# MINI_MAST.net
KiCad netlist of a schematic drawn in EAGLE
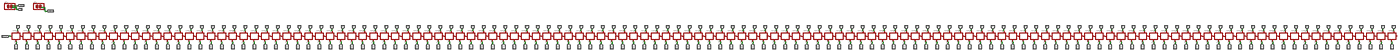
[diagram p0: schematic, sheet 1, overview]
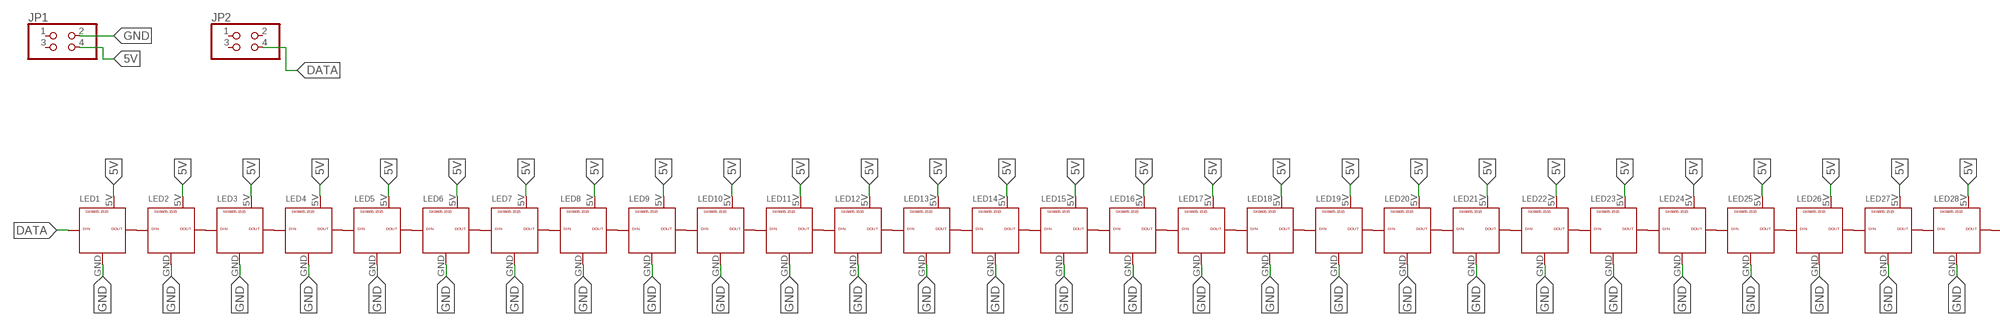
[diagram p1: schematic, sheet 1, part 1 of 6]
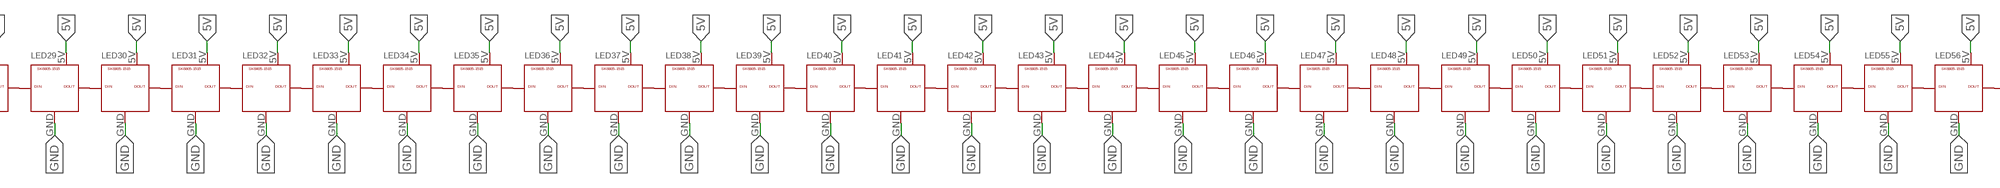
[diagram p2: schematic, sheet 1, part 2 of 6]
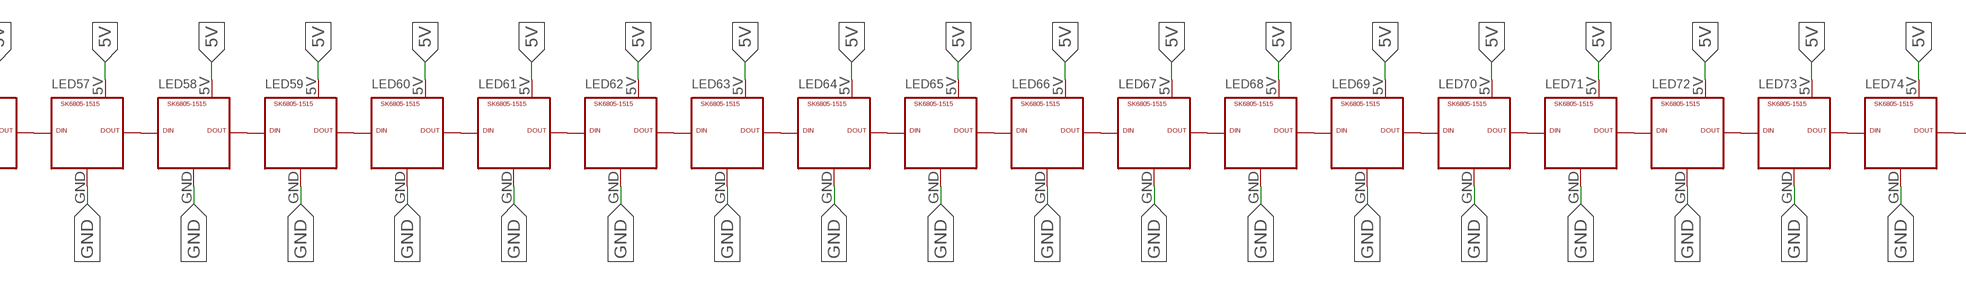
[diagram p3: schematic, sheet 1, part 3 of 6]
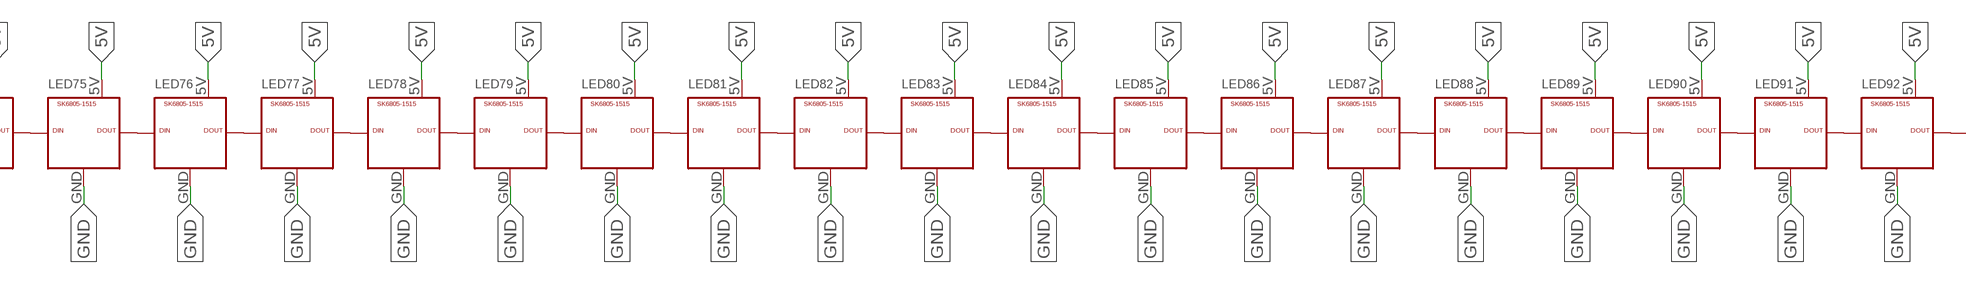
[diagram p4: schematic, sheet 1, part 4 of 6]
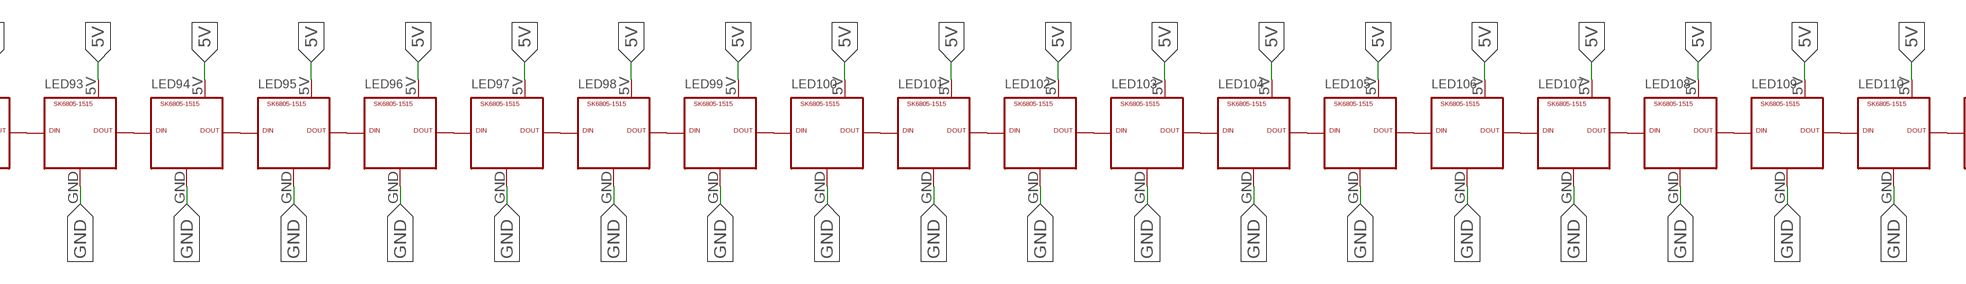
[diagram p5: schematic, sheet 1, part 5 of 6]
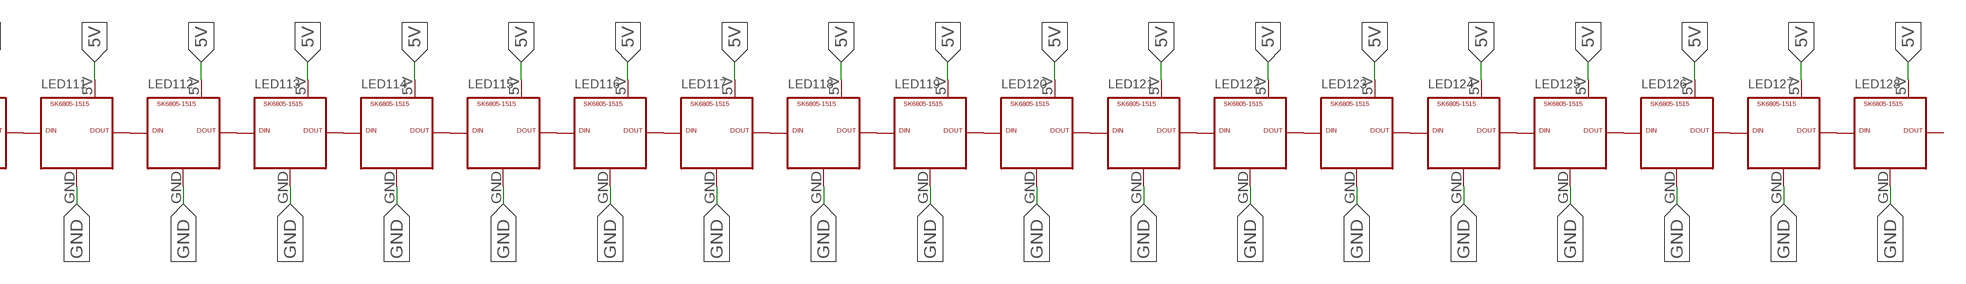
[diagram p6: schematic, sheet 1, part 6 of 6]

(export (version "E")
  (design (tool "Eeschema 10.0.6"))
  (components
    (comp (ref "JP1")
      (value "PINHD-2X2/90")
      (footprint "eagle-import:2X02_90")
      (libsource (lib "eagle-import") (part "PINHD-2X2/90"))
    )
    (comp (ref "JP2")
      (value "PINHD-2X2/90")
      (footprint "eagle-import:2X02_90")
      (libsource (lib "eagle-import") (part "PINHD-2X2/90"))
    )
    (comp (ref "LED1")
      (value "SK6805-1515")
      (footprint "eagle-import:1515")
      (libsource (lib "eagle-import") (part "SK6805-1515"))
    )
    (comp (ref "LED2")
      (value "SK6805-1515")
      (footprint "eagle-import:1515")
      (libsource (lib "eagle-import") (part "SK6805-1515"))
    )
    (comp (ref "LED3")
      (value "SK6805-1515")
      (footprint "eagle-import:1515")
      (libsource (lib "eagle-import") (part "SK6805-1515"))
    )
    (comp (ref "LED4")
      (value "SK6805-1515")
      (footprint "eagle-import:1515")
      (libsource (lib "eagle-import") (part "SK6805-1515"))
    )
    (comp (ref "LED5")
      (value "SK6805-1515")
      (footprint "eagle-import:1515")
      (libsource (lib "eagle-import") (part "SK6805-1515"))
    )
    (comp (ref "LED6")
      (value "SK6805-1515")
      (footprint "eagle-import:1515")
      (libsource (lib "eagle-import") (part "SK6805-1515"))
    )
    (comp (ref "LED7")
      (value "SK6805-1515")
      (footprint "eagle-import:1515")
      (libsource (lib "eagle-import") (part "SK6805-1515"))
    )
    (comp (ref "LED8")
      (value "SK6805-1515")
      (footprint "eagle-import:1515")
      (libsource (lib "eagle-import") (part "SK6805-1515"))
    )
    (comp (ref "LED9")
      (value "SK6805-1515")
      (footprint "eagle-import:1515")
      (libsource (lib "eagle-import") (part "SK6805-1515"))
    )
    (comp (ref "LED10")
      (value "SK6805-1515")
      (footprint "eagle-import:1515")
      (libsource (lib "eagle-import") (part "SK6805-1515"))
    )
    (comp (ref "LED11")
      (value "SK6805-1515")
      (footprint "eagle-import:1515")
      (libsource (lib "eagle-import") (part "SK6805-1515"))
    )
    (comp (ref "LED12")
      (value "SK6805-1515")
      (footprint "eagle-import:1515")
      (libsource (lib "eagle-import") (part "SK6805-1515"))
    )
    (comp (ref "LED13")
      (value "SK6805-1515")
      (footprint "eagle-import:1515")
      (libsource (lib "eagle-import") (part "SK6805-1515"))
    )
    (comp (ref "LED14")
      (value "SK6805-1515")
      (footprint "eagle-import:1515")
      (libsource (lib "eagle-import") (part "SK6805-1515"))
    )
    (comp (ref "LED15")
      (value "SK6805-1515")
      (footprint "eagle-import:1515")
      (libsource (lib "eagle-import") (part "SK6805-1515"))
    )
    (comp (ref "LED16")
      (value "SK6805-1515")
      (footprint "eagle-import:1515")
      (libsource (lib "eagle-import") (part "SK6805-1515"))
    )
    (comp (ref "LED17")
      (value "SK6805-1515")
      (footprint "eagle-import:1515")
      (libsource (lib "eagle-import") (part "SK6805-1515"))
    )
    (comp (ref "LED18")
      (value "SK6805-1515")
      (footprint "eagle-import:1515")
      (libsource (lib "eagle-import") (part "SK6805-1515"))
    )
    (comp (ref "LED19")
      (value "SK6805-1515")
      (footprint "eagle-import:1515")
      (libsource (lib "eagle-import") (part "SK6805-1515"))
    )
    (comp (ref "LED20")
      (value "SK6805-1515")
      (footprint "eagle-import:1515")
      (libsource (lib "eagle-import") (part "SK6805-1515"))
    )
    (comp (ref "LED21")
      (value "SK6805-1515")
      (footprint "eagle-import:1515")
      (libsource (lib "eagle-import") (part "SK6805-1515"))
    )
    (comp (ref "LED22")
      (value "SK6805-1515")
      (footprint "eagle-import:1515")
      (libsource (lib "eagle-import") (part "SK6805-1515"))
    )
    (comp (ref "LED23")
      (value "SK6805-1515")
      (footprint "eagle-import:1515")
      (libsource (lib "eagle-import") (part "SK6805-1515"))
    )
    (comp (ref "LED24")
      (value "SK6805-1515")
      (footprint "eagle-import:1515")
      (libsource (lib "eagle-import") (part "SK6805-1515"))
    )
    (comp (ref "LED25")
      (value "SK6805-1515")
      (footprint "eagle-import:1515")
      (libsource (lib "eagle-import") (part "SK6805-1515"))
    )
    (comp (ref "LED26")
      (value "SK6805-1515")
      (footprint "eagle-import:1515")
      (libsource (lib "eagle-import") (part "SK6805-1515"))
    )
    (comp (ref "LED27")
      (value "SK6805-1515")
      (footprint "eagle-import:1515")
      (libsource (lib "eagle-import") (part "SK6805-1515"))
    )
    (comp (ref "LED28")
      (value "SK6805-1515")
      (footprint "eagle-import:1515")
      (libsource (lib "eagle-import") (part "SK6805-1515"))
    )
    (comp (ref "LED29")
      (value "SK6805-1515")
      (footprint "eagle-import:1515")
      (libsource (lib "eagle-import") (part "SK6805-1515"))
    )
    (comp (ref "LED30")
      (value "SK6805-1515")
      (footprint "eagle-import:1515")
      (libsource (lib "eagle-import") (part "SK6805-1515"))
    )
    (comp (ref "LED31")
      (value "SK6805-1515")
      (footprint "eagle-import:1515")
      (libsource (lib "eagle-import") (part "SK6805-1515"))
    )
    (comp (ref "LED32")
      (value "SK6805-1515")
      (footprint "eagle-import:1515")
      (libsource (lib "eagle-import") (part "SK6805-1515"))
    )
    (comp (ref "LED33")
      (value "SK6805-1515")
      (footprint "eagle-import:1515")
      (libsource (lib "eagle-import") (part "SK6805-1515"))
    )
    (comp (ref "LED34")
      (value "SK6805-1515")
      (footprint "eagle-import:1515")
      (libsource (lib "eagle-import") (part "SK6805-1515"))
    )
    (comp (ref "LED35")
      (value "SK6805-1515")
      (footprint "eagle-import:1515")
      (libsource (lib "eagle-import") (part "SK6805-1515"))
    )
    (comp (ref "LED36")
      (value "SK6805-1515")
      (footprint "eagle-import:1515")
      (libsource (lib "eagle-import") (part "SK6805-1515"))
    )
    (comp (ref "LED37")
      (value "SK6805-1515")
      (footprint "eagle-import:1515")
      (libsource (lib "eagle-import") (part "SK6805-1515"))
    )
    (comp (ref "LED38")
      (value "SK6805-1515")
      (footprint "eagle-import:1515")
      (libsource (lib "eagle-import") (part "SK6805-1515"))
    )
    (comp (ref "LED39")
      (value "SK6805-1515")
      (footprint "eagle-import:1515")
      (libsource (lib "eagle-import") (part "SK6805-1515"))
    )
    (comp (ref "LED40")
      (value "SK6805-1515")
      (footprint "eagle-import:1515")
      (libsource (lib "eagle-import") (part "SK6805-1515"))
    )
    (comp (ref "LED41")
      (value "SK6805-1515")
      (footprint "eagle-import:1515")
      (libsource (lib "eagle-import") (part "SK6805-1515"))
    )
    (comp (ref "LED42")
      (value "SK6805-1515")
      (footprint "eagle-import:1515")
      (libsource (lib "eagle-import") (part "SK6805-1515"))
    )
    (comp (ref "LED43")
      (value "SK6805-1515")
      (footprint "eagle-import:1515")
      (libsource (lib "eagle-import") (part "SK6805-1515"))
    )
    (comp (ref "LED44")
      (value "SK6805-1515")
      (footprint "eagle-import:1515")
      (libsource (lib "eagle-import") (part "SK6805-1515"))
    )
    (comp (ref "LED45")
      (value "SK6805-1515")
      (footprint "eagle-import:1515")
      (libsource (lib "eagle-import") (part "SK6805-1515"))
    )
    (comp (ref "LED46")
      (value "SK6805-1515")
      (footprint "eagle-import:1515")
      (libsource (lib "eagle-import") (part "SK6805-1515"))
    )
    (comp (ref "LED47")
      (value "SK6805-1515")
      (footprint "eagle-import:1515")
      (libsource (lib "eagle-import") (part "SK6805-1515"))
    )
    (comp (ref "LED48")
      (value "SK6805-1515")
      (footprint "eagle-import:1515")
      (libsource (lib "eagle-import") (part "SK6805-1515"))
    )
    (comp (ref "LED49")
      (value "SK6805-1515")
      (footprint "eagle-import:1515")
      (libsource (lib "eagle-import") (part "SK6805-1515"))
    )
    (comp (ref "LED50")
      (value "SK6805-1515")
      (footprint "eagle-import:1515")
      (libsource (lib "eagle-import") (part "SK6805-1515"))
    )
    (comp (ref "LED51")
      (value "SK6805-1515")
      (footprint "eagle-import:1515")
      (libsource (lib "eagle-import") (part "SK6805-1515"))
    )
    (comp (ref "LED52")
      (value "SK6805-1515")
      (footprint "eagle-import:1515")
      (libsource (lib "eagle-import") (part "SK6805-1515"))
    )
    (comp (ref "LED53")
      (value "SK6805-1515")
      (footprint "eagle-import:1515")
      (libsource (lib "eagle-import") (part "SK6805-1515"))
    )
    (comp (ref "LED54")
      (value "SK6805-1515")
      (footprint "eagle-import:1515")
      (libsource (lib "eagle-import") (part "SK6805-1515"))
    )
    (comp (ref "LED55")
      (value "SK6805-1515")
      (footprint "eagle-import:1515")
      (libsource (lib "eagle-import") (part "SK6805-1515"))
    )
    (comp (ref "LED56")
      (value "SK6805-1515")
      (footprint "eagle-import:1515")
      (libsource (lib "eagle-import") (part "SK6805-1515"))
    )
    (comp (ref "LED57")
      (value "SK6805-1515")
      (footprint "eagle-import:1515")
      (libsource (lib "eagle-import") (part "SK6805-1515"))
    )
    (comp (ref "LED58")
      (value "SK6805-1515")
      (footprint "eagle-import:1515")
      (libsource (lib "eagle-import") (part "SK6805-1515"))
    )
    (comp (ref "LED59")
      (value "SK6805-1515")
      (footprint "eagle-import:1515")
      (libsource (lib "eagle-import") (part "SK6805-1515"))
    )
    (comp (ref "LED60")
      (value "SK6805-1515")
      (footprint "eagle-import:1515")
      (libsource (lib "eagle-import") (part "SK6805-1515"))
    )
    (comp (ref "LED61")
      (value "SK6805-1515")
      (footprint "eagle-import:1515")
      (libsource (lib "eagle-import") (part "SK6805-1515"))
    )
    (comp (ref "LED62")
      (value "SK6805-1515")
      (footprint "eagle-import:1515")
      (libsource (lib "eagle-import") (part "SK6805-1515"))
    )
    (comp (ref "LED63")
      (value "SK6805-1515")
      (footprint "eagle-import:1515")
      (libsource (lib "eagle-import") (part "SK6805-1515"))
    )
    (comp (ref "LED64")
      (value "SK6805-1515")
      (footprint "eagle-import:1515")
      (libsource (lib "eagle-import") (part "SK6805-1515"))
    )
    (comp (ref "LED65")
      (value "SK6805-1515")
      (footprint "eagle-import:1515")
      (libsource (lib "eagle-import") (part "SK6805-1515"))
    )
    (comp (ref "LED66")
      (value "SK6805-1515")
      (footprint "eagle-import:1515")
      (libsource (lib "eagle-import") (part "SK6805-1515"))
    )
    (comp (ref "LED67")
      (value "SK6805-1515")
      (footprint "eagle-import:1515")
      (libsource (lib "eagle-import") (part "SK6805-1515"))
    )
    (comp (ref "LED68")
      (value "SK6805-1515")
      (footprint "eagle-import:1515")
      (libsource (lib "eagle-import") (part "SK6805-1515"))
    )
    (comp (ref "LED69")
      (value "SK6805-1515")
      (footprint "eagle-import:1515")
      (libsource (lib "eagle-import") (part "SK6805-1515"))
    )
    (comp (ref "LED70")
      (value "SK6805-1515")
      (footprint "eagle-import:1515")
      (libsource (lib "eagle-import") (part "SK6805-1515"))
    )
    (comp (ref "LED71")
      (value "SK6805-1515")
      (footprint "eagle-import:1515")
      (libsource (lib "eagle-import") (part "SK6805-1515"))
    )
    (comp (ref "LED72")
      (value "SK6805-1515")
      (footprint "eagle-import:1515")
      (libsource (lib "eagle-import") (part "SK6805-1515"))
    )
    (comp (ref "LED73")
      (value "SK6805-1515")
      (footprint "eagle-import:1515")
      (libsource (lib "eagle-import") (part "SK6805-1515"))
    )
    (comp (ref "LED74")
      (value "SK6805-1515")
      (footprint "eagle-import:1515")
      (libsource (lib "eagle-import") (part "SK6805-1515"))
    )
    (comp (ref "LED75")
      (value "SK6805-1515")
      (footprint "eagle-import:1515")
      (libsource (lib "eagle-import") (part "SK6805-1515"))
    )
    (comp (ref "LED76")
      (value "SK6805-1515")
      (footprint "eagle-import:1515")
      (libsource (lib "eagle-import") (part "SK6805-1515"))
    )
    (comp (ref "LED77")
      (value "SK6805-1515")
      (footprint "eagle-import:1515")
      (libsource (lib "eagle-import") (part "SK6805-1515"))
    )
    (comp (ref "LED78")
      (value "SK6805-1515")
      (footprint "eagle-import:1515")
      (libsource (lib "eagle-import") (part "SK6805-1515"))
    )
    (comp (ref "LED79")
      (value "SK6805-1515")
      (footprint "eagle-import:1515")
      (libsource (lib "eagle-import") (part "SK6805-1515"))
    )
    (comp (ref "LED80")
      (value "SK6805-1515")
      (footprint "eagle-import:1515")
      (libsource (lib "eagle-import") (part "SK6805-1515"))
    )
    (comp (ref "LED81")
      (value "SK6805-1515")
      (footprint "eagle-import:1515")
      (libsource (lib "eagle-import") (part "SK6805-1515"))
    )
    (comp (ref "LED82")
      (value "SK6805-1515")
      (footprint "eagle-import:1515")
      (libsource (lib "eagle-import") (part "SK6805-1515"))
    )
    (comp (ref "LED83")
      (value "SK6805-1515")
      (footprint "eagle-import:1515")
      (libsource (lib "eagle-import") (part "SK6805-1515"))
    )
    (comp (ref "LED84")
      (value "SK6805-1515")
      (footprint "eagle-import:1515")
      (libsource (lib "eagle-import") (part "SK6805-1515"))
    )
    (comp (ref "LED85")
      (value "SK6805-1515")
      (footprint "eagle-import:1515")
      (libsource (lib "eagle-import") (part "SK6805-1515"))
    )
    (comp (ref "LED86")
      (value "SK6805-1515")
      (footprint "eagle-import:1515")
      (libsource (lib "eagle-import") (part "SK6805-1515"))
    )
    (comp (ref "LED87")
      (value "SK6805-1515")
      (footprint "eagle-import:1515")
      (libsource (lib "eagle-import") (part "SK6805-1515"))
    )
    (comp (ref "LED88")
      (value "SK6805-1515")
      (footprint "eagle-import:1515")
      (libsource (lib "eagle-import") (part "SK6805-1515"))
    )
    (comp (ref "LED89")
      (value "SK6805-1515")
      (footprint "eagle-import:1515")
      (libsource (lib "eagle-import") (part "SK6805-1515"))
    )
    (comp (ref "LED90")
      (value "SK6805-1515")
      (footprint "eagle-import:1515")
      (libsource (lib "eagle-import") (part "SK6805-1515"))
    )
    (comp (ref "LED91")
      (value "SK6805-1515")
      (footprint "eagle-import:1515")
      (libsource (lib "eagle-import") (part "SK6805-1515"))
    )
    (comp (ref "LED92")
      (value "SK6805-1515")
      (footprint "eagle-import:1515")
      (libsource (lib "eagle-import") (part "SK6805-1515"))
    )
    (comp (ref "LED93")
      (value "SK6805-1515")
      (footprint "eagle-import:1515")
      (libsource (lib "eagle-import") (part "SK6805-1515"))
    )
    (comp (ref "LED94")
      (value "SK6805-1515")
      (footprint "eagle-import:1515")
      (libsource (lib "eagle-import") (part "SK6805-1515"))
    )
    (comp (ref "LED95")
      (value "SK6805-1515")
      (footprint "eagle-import:1515")
      (libsource (lib "eagle-import") (part "SK6805-1515"))
    )
    (comp (ref "LED96")
      (value "SK6805-1515")
      (footprint "eagle-import:1515")
      (libsource (lib "eagle-import") (part "SK6805-1515"))
    )
    (comp (ref "LED97")
      (value "SK6805-1515")
      (footprint "eagle-import:1515")
      (libsource (lib "eagle-import") (part "SK6805-1515"))
    )
    (comp (ref "LED98")
      (value "SK6805-1515")
      (footprint "eagle-import:1515")
      (libsource (lib "eagle-import") (part "SK6805-1515"))
    )
    (comp (ref "LED99")
      (value "SK6805-1515")
      (footprint "eagle-import:1515")
      (libsource (lib "eagle-import") (part "SK6805-1515"))
    )
    (comp (ref "LED100")
      (value "SK6805-1515")
      (footprint "eagle-import:1515")
      (libsource (lib "eagle-import") (part "SK6805-1515"))
    )
    (comp (ref "LED101")
      (value "SK6805-1515")
      (footprint "eagle-import:1515")
      (libsource (lib "eagle-import") (part "SK6805-1515"))
    )
    (comp (ref "LED102")
      (value "SK6805-1515")
      (footprint "eagle-import:1515")
      (libsource (lib "eagle-import") (part "SK6805-1515"))
    )
    (comp (ref "LED103")
      (value "SK6805-1515")
      (footprint "eagle-import:1515")
      (libsource (lib "eagle-import") (part "SK6805-1515"))
    )
    (comp (ref "LED104")
      (value "SK6805-1515")
      (footprint "eagle-import:1515")
      (libsource (lib "eagle-import") (part "SK6805-1515"))
    )
    (comp (ref "LED105")
      (value "SK6805-1515")
      (footprint "eagle-import:1515")
      (libsource (lib "eagle-import") (part "SK6805-1515"))
    )
    (comp (ref "LED106")
      (value "SK6805-1515")
      (footprint "eagle-import:1515")
      (libsource (lib "eagle-import") (part "SK6805-1515"))
    )
    (comp (ref "LED107")
      (value "SK6805-1515")
      (footprint "eagle-import:1515")
      (libsource (lib "eagle-import") (part "SK6805-1515"))
    )
    (comp (ref "LED108")
      (value "SK6805-1515")
      (footprint "eagle-import:1515")
      (libsource (lib "eagle-import") (part "SK6805-1515"))
    )
    (comp (ref "LED109")
      (value "SK6805-1515")
      (footprint "eagle-import:1515")
      (libsource (lib "eagle-import") (part "SK6805-1515"))
    )
    (comp (ref "LED110")
      (value "SK6805-1515")
      (footprint "eagle-import:1515")
      (libsource (lib "eagle-import") (part "SK6805-1515"))
    )
    (comp (ref "LED111")
      (value "SK6805-1515")
      (footprint "eagle-import:1515")
      (libsource (lib "eagle-import") (part "SK6805-1515"))
    )
    (comp (ref "LED112")
      (value "SK6805-1515")
      (footprint "eagle-import:1515")
      (libsource (lib "eagle-import") (part "SK6805-1515"))
    )
    (comp (ref "LED113")
      (value "SK6805-1515")
      (footprint "eagle-import:1515")
      (libsource (lib "eagle-import") (part "SK6805-1515"))
    )
    (comp (ref "LED114")
      (value "SK6805-1515")
      (footprint "eagle-import:1515")
      (libsource (lib "eagle-import") (part "SK6805-1515"))
    )
    (comp (ref "LED115")
      (value "SK6805-1515")
      (footprint "eagle-import:1515")
      (libsource (lib "eagle-import") (part "SK6805-1515"))
    )
    (comp (ref "LED116")
      (value "SK6805-1515")
      (footprint "eagle-import:1515")
      (libsource (lib "eagle-import") (part "SK6805-1515"))
    )
    (comp (ref "LED117")
      (value "SK6805-1515")
      (footprint "eagle-import:1515")
      (libsource (lib "eagle-import") (part "SK6805-1515"))
    )
    (comp (ref "LED118")
      (value "SK6805-1515")
      (footprint "eagle-import:1515")
      (libsource (lib "eagle-import") (part "SK6805-1515"))
    )
    (comp (ref "LED119")
      (value "SK6805-1515")
      (footprint "eagle-import:1515")
      (libsource (lib "eagle-import") (part "SK6805-1515"))
    )
    (comp (ref "LED120")
      (value "SK6805-1515")
      (footprint "eagle-import:1515")
      (libsource (lib "eagle-import") (part "SK6805-1515"))
    )
    (comp (ref "LED121")
      (value "SK6805-1515")
      (footprint "eagle-import:1515")
      (libsource (lib "eagle-import") (part "SK6805-1515"))
    )
    (comp (ref "LED122")
      (value "SK6805-1515")
      (footprint "eagle-import:1515")
      (libsource (lib "eagle-import") (part "SK6805-1515"))
    )
    (comp (ref "LED123")
      (value "SK6805-1515")
      (footprint "eagle-import:1515")
      (libsource (lib "eagle-import") (part "SK6805-1515"))
    )
    (comp (ref "LED124")
      (value "SK6805-1515")
      (footprint "eagle-import:1515")
      (libsource (lib "eagle-import") (part "SK6805-1515"))
    )
    (comp (ref "LED125")
      (value "SK6805-1515")
      (footprint "eagle-import:1515")
      (libsource (lib "eagle-import") (part "SK6805-1515"))
    )
    (comp (ref "LED126")
      (value "SK6805-1515")
      (footprint "eagle-import:1515")
      (libsource (lib "eagle-import") (part "SK6805-1515"))
    )
    (comp (ref "LED127")
      (value "SK6805-1515")
      (footprint "eagle-import:1515")
      (libsource (lib "eagle-import") (part "SK6805-1515"))
    )
    (comp (ref "LED128")
      (value "SK6805-1515")
      (footprint "eagle-import:1515")
      (libsource (lib "eagle-import") (part "SK6805-1515"))
    )
  )
  (nets
    (net (code "1") (name "5V") (class "Default")
      (node (ref "JP1") (pin "4") (pinfunction "4_4") (pintype "passive"))
      (node (ref "LED1") (pin "5V") (pinfunction "5V_5V") (pintype "power_in"))
      (node (ref "LED10") (pin "5V") (pinfunction "5V_5V") (pintype "power_in"))
      (node (ref "LED100") (pin "5V") (pinfunction "5V_5V") (pintype "power_in"))
      (node (ref "LED101") (pin "5V") (pinfunction "5V_5V") (pintype "power_in"))
      (node (ref "LED102") (pin "5V") (pinfunction "5V_5V") (pintype "power_in"))
      (node (ref "LED103") (pin "5V") (pinfunction "5V_5V") (pintype "power_in"))
      (node (ref "LED104") (pin "5V") (pinfunction "5V_5V") (pintype "power_in"))
      (node (ref "LED105") (pin "5V") (pinfunction "5V_5V") (pintype "power_in"))
      (node (ref "LED106") (pin "5V") (pinfunction "5V_5V") (pintype "power_in"))
      (node (ref "LED107") (pin "5V") (pinfunction "5V_5V") (pintype "power_in"))
      (node (ref "LED108") (pin "5V") (pinfunction "5V_5V") (pintype "power_in"))
      (node (ref "LED109") (pin "5V") (pinfunction "5V_5V") (pintype "power_in"))
      (node (ref "LED11") (pin "5V") (pinfunction "5V_5V") (pintype "power_in"))
      (node (ref "LED110") (pin "5V") (pinfunction "5V_5V") (pintype "power_in"))
      (node (ref "LED111") (pin "5V") (pinfunction "5V_5V") (pintype "power_in"))
      (node (ref "LED112") (pin "5V") (pinfunction "5V_5V") (pintype "power_in"))
      (node (ref "LED113") (pin "5V") (pinfunction "5V_5V") (pintype "power_in"))
      (node (ref "LED114") (pin "5V") (pinfunction "5V_5V") (pintype "power_in"))
      (node (ref "LED115") (pin "5V") (pinfunction "5V_5V") (pintype "power_in"))
      (node (ref "LED116") (pin "5V") (pinfunction "5V_5V") (pintype "power_in"))
      (node (ref "LED117") (pin "5V") (pinfunction "5V_5V") (pintype "power_in"))
      (node (ref "LED118") (pin "5V") (pinfunction "5V_5V") (pintype "power_in"))
      (node (ref "LED119") (pin "5V") (pinfunction "5V_5V") (pintype "power_in"))
      (node (ref "LED12") (pin "5V") (pinfunction "5V_5V") (pintype "power_in"))
      (node (ref "LED120") (pin "5V") (pinfunction "5V_5V") (pintype "power_in"))
      (node (ref "LED121") (pin "5V") (pinfunction "5V_5V") (pintype "power_in"))
      (node (ref "LED122") (pin "5V") (pinfunction "5V_5V") (pintype "power_in"))
      (node (ref "LED123") (pin "5V") (pinfunction "5V_5V") (pintype "power_in"))
      (node (ref "LED124") (pin "5V") (pinfunction "5V_5V") (pintype "power_in"))
      (node (ref "LED125") (pin "5V") (pinfunction "5V_5V") (pintype "power_in"))
      (node (ref "LED126") (pin "5V") (pinfunction "5V_5V") (pintype "power_in"))
      (node (ref "LED127") (pin "5V") (pinfunction "5V_5V") (pintype "power_in"))
      (node (ref "LED128") (pin "5V") (pinfunction "5V_5V") (pintype "power_in"))
      (node (ref "LED13") (pin "5V") (pinfunction "5V_5V") (pintype "power_in"))
      (node (ref "LED14") (pin "5V") (pinfunction "5V_5V") (pintype "power_in"))
      (node (ref "LED15") (pin "5V") (pinfunction "5V_5V") (pintype "power_in"))
      (node (ref "LED16") (pin "5V") (pinfunction "5V_5V") (pintype "power_in"))
      (node (ref "LED17") (pin "5V") (pinfunction "5V_5V") (pintype "power_in"))
      (node (ref "LED18") (pin "5V") (pinfunction "5V_5V") (pintype "power_in"))
      (node (ref "LED19") (pin "5V") (pinfunction "5V_5V") (pintype "power_in"))
      (node (ref "LED2") (pin "5V") (pinfunction "5V_5V") (pintype "power_in"))
      (node (ref "LED20") (pin "5V") (pinfunction "5V_5V") (pintype "power_in"))
      (node (ref "LED21") (pin "5V") (pinfunction "5V_5V") (pintype "power_in"))
      (node (ref "LED22") (pin "5V") (pinfunction "5V_5V") (pintype "power_in"))
      (node (ref "LED23") (pin "5V") (pinfunction "5V_5V") (pintype "power_in"))
      (node (ref "LED24") (pin "5V") (pinfunction "5V_5V") (pintype "power_in"))
      (node (ref "LED25") (pin "5V") (pinfunction "5V_5V") (pintype "power_in"))
      (node (ref "LED26") (pin "5V") (pinfunction "5V_5V") (pintype "power_in"))
      (node (ref "LED27") (pin "5V") (pinfunction "5V_5V") (pintype "power_in"))
      (node (ref "LED28") (pin "5V") (pinfunction "5V_5V") (pintype "power_in"))
      (node (ref "LED29") (pin "5V") (pinfunction "5V_5V") (pintype "power_in"))
      (node (ref "LED3") (pin "5V") (pinfunction "5V_5V") (pintype "power_in"))
      (node (ref "LED30") (pin "5V") (pinfunction "5V_5V") (pintype "power_in"))
      (node (ref "LED31") (pin "5V") (pinfunction "5V_5V") (pintype "power_in"))
      (node (ref "LED32") (pin "5V") (pinfunction "5V_5V") (pintype "power_in"))
      (node (ref "LED33") (pin "5V") (pinfunction "5V_5V") (pintype "power_in"))
      (node (ref "LED34") (pin "5V") (pinfunction "5V_5V") (pintype "power_in"))
      (node (ref "LED35") (pin "5V") (pinfunction "5V_5V") (pintype "power_in"))
      (node (ref "LED36") (pin "5V") (pinfunction "5V_5V") (pintype "power_in"))
      (node (ref "LED37") (pin "5V") (pinfunction "5V_5V") (pintype "power_in"))
      (node (ref "LED38") (pin "5V") (pinfunction "5V_5V") (pintype "power_in"))
      (node (ref "LED39") (pin "5V") (pinfunction "5V_5V") (pintype "power_in"))
      (node (ref "LED4") (pin "5V") (pinfunction "5V_5V") (pintype "power_in"))
      (node (ref "LED40") (pin "5V") (pinfunction "5V_5V") (pintype "power_in"))
      (node (ref "LED41") (pin "5V") (pinfunction "5V_5V") (pintype "power_in"))
      (node (ref "LED42") (pin "5V") (pinfunction "5V_5V") (pintype "power_in"))
      (node (ref "LED43") (pin "5V") (pinfunction "5V_5V") (pintype "power_in"))
      (node (ref "LED44") (pin "5V") (pinfunction "5V_5V") (pintype "power_in"))
      (node (ref "LED45") (pin "5V") (pinfunction "5V_5V") (pintype "power_in"))
      (node (ref "LED46") (pin "5V") (pinfunction "5V_5V") (pintype "power_in"))
      (node (ref "LED47") (pin "5V") (pinfunction "5V_5V") (pintype "power_in"))
      (node (ref "LED48") (pin "5V") (pinfunction "5V_5V") (pintype "power_in"))
      (node (ref "LED49") (pin "5V") (pinfunction "5V_5V") (pintype "power_in"))
      (node (ref "LED5") (pin "5V") (pinfunction "5V_5V") (pintype "power_in"))
      (node (ref "LED50") (pin "5V") (pinfunction "5V_5V") (pintype "power_in"))
      (node (ref "LED51") (pin "5V") (pinfunction "5V_5V") (pintype "power_in"))
      (node (ref "LED52") (pin "5V") (pinfunction "5V_5V") (pintype "power_in"))
      (node (ref "LED53") (pin "5V") (pinfunction "5V_5V") (pintype "power_in"))
      (node (ref "LED54") (pin "5V") (pinfunction "5V_5V") (pintype "power_in"))
      (node (ref "LED55") (pin "5V") (pinfunction "5V_5V") (pintype "power_in"))
      (node (ref "LED56") (pin "5V") (pinfunction "5V_5V") (pintype "power_in"))
      (node (ref "LED57") (pin "5V") (pinfunction "5V_5V") (pintype "power_in"))
      (node (ref "LED58") (pin "5V") (pinfunction "5V_5V") (pintype "power_in"))
      (node (ref "LED59") (pin "5V") (pinfunction "5V_5V") (pintype "power_in"))
      (node (ref "LED6") (pin "5V") (pinfunction "5V_5V") (pintype "power_in"))
      (node (ref "LED60") (pin "5V") (pinfunction "5V_5V") (pintype "power_in"))
      (node (ref "LED61") (pin "5V") (pinfunction "5V_5V") (pintype "power_in"))
      (node (ref "LED62") (pin "5V") (pinfunction "5V_5V") (pintype "power_in"))
      (node (ref "LED63") (pin "5V") (pinfunction "5V_5V") (pintype "power_in"))
      (node (ref "LED64") (pin "5V") (pinfunction "5V_5V") (pintype "power_in"))
      (node (ref "LED65") (pin "5V") (pinfunction "5V_5V") (pintype "power_in"))
      (node (ref "LED66") (pin "5V") (pinfunction "5V_5V") (pintype "power_in"))
      (node (ref "LED67") (pin "5V") (pinfunction "5V_5V") (pintype "power_in"))
      (node (ref "LED68") (pin "5V") (pinfunction "5V_5V") (pintype "power_in"))
      (node (ref "LED69") (pin "5V") (pinfunction "5V_5V") (pintype "power_in"))
      (node (ref "LED7") (pin "5V") (pinfunction "5V_5V") (pintype "power_in"))
      (node (ref "LED70") (pin "5V") (pinfunction "5V_5V") (pintype "power_in"))
      (node (ref "LED71") (pin "5V") (pinfunction "5V_5V") (pintype "power_in"))
      (node (ref "LED72") (pin "5V") (pinfunction "5V_5V") (pintype "power_in"))
      (node (ref "LED73") (pin "5V") (pinfunction "5V_5V") (pintype "power_in"))
      (node (ref "LED74") (pin "5V") (pinfunction "5V_5V") (pintype "power_in"))
      (node (ref "LED75") (pin "5V") (pinfunction "5V_5V") (pintype "power_in"))
      (node (ref "LED76") (pin "5V") (pinfunction "5V_5V") (pintype "power_in"))
      (node (ref "LED77") (pin "5V") (pinfunction "5V_5V") (pintype "power_in"))
      (node (ref "LED78") (pin "5V") (pinfunction "5V_5V") (pintype "power_in"))
      (node (ref "LED79") (pin "5V") (pinfunction "5V_5V") (pintype "power_in"))
      (node (ref "LED8") (pin "5V") (pinfunction "5V_5V") (pintype "power_in"))
      (node (ref "LED80") (pin "5V") (pinfunction "5V_5V") (pintype "power_in"))
      (node (ref "LED81") (pin "5V") (pinfunction "5V_5V") (pintype "power_in"))
      (node (ref "LED82") (pin "5V") (pinfunction "5V_5V") (pintype "power_in"))
      (node (ref "LED83") (pin "5V") (pinfunction "5V_5V") (pintype "power_in"))
      (node (ref "LED84") (pin "5V") (pinfunction "5V_5V") (pintype "power_in"))
      (node (ref "LED85") (pin "5V") (pinfunction "5V_5V") (pintype "power_in"))
      (node (ref "LED86") (pin "5V") (pinfunction "5V_5V") (pintype "power_in"))
      (node (ref "LED87") (pin "5V") (pinfunction "5V_5V") (pintype "power_in"))
      (node (ref "LED88") (pin "5V") (pinfunction "5V_5V") (pintype "power_in"))
      (node (ref "LED89") (pin "5V") (pinfunction "5V_5V") (pintype "power_in"))
      (node (ref "LED9") (pin "5V") (pinfunction "5V_5V") (pintype "power_in"))
      (node (ref "LED90") (pin "5V") (pinfunction "5V_5V") (pintype "power_in"))
      (node (ref "LED91") (pin "5V") (pinfunction "5V_5V") (pintype "power_in"))
      (node (ref "LED92") (pin "5V") (pinfunction "5V_5V") (pintype "power_in"))
      (node (ref "LED93") (pin "5V") (pinfunction "5V_5V") (pintype "power_in"))
      (node (ref "LED94") (pin "5V") (pinfunction "5V_5V") (pintype "power_in"))
      (node (ref "LED95") (pin "5V") (pinfunction "5V_5V") (pintype "power_in"))
      (node (ref "LED96") (pin "5V") (pinfunction "5V_5V") (pintype "power_in"))
      (node (ref "LED97") (pin "5V") (pinfunction "5V_5V") (pintype "power_in"))
      (node (ref "LED98") (pin "5V") (pinfunction "5V_5V") (pintype "power_in"))
      (node (ref "LED99") (pin "5V") (pinfunction "5V_5V") (pintype "power_in"))
    )
    (net (code "2") (name "DATA") (class "Default")
      (node (ref "JP2") (pin "4") (pinfunction "4_4") (pintype "passive"))
      (node (ref "LED1") (pin "DIN") (pinfunction "DIN_DIN") (pintype "bidirectional"))
    )
    (net (code "3") (name "GND") (class "Default")
      (node (ref "JP1") (pin "2") (pinfunction "2_2") (pintype "passive"))
      (node (ref "LED1") (pin "GND") (pinfunction "GND_GND") (pintype "power_in"))
      (node (ref "LED10") (pin "GND") (pinfunction "GND_GND") (pintype "power_in"))
      (node (ref "LED100") (pin "GND") (pinfunction "GND_GND") (pintype "power_in"))
      (node (ref "LED101") (pin "GND") (pinfunction "GND_GND") (pintype "power_in"))
      (node (ref "LED102") (pin "GND") (pinfunction "GND_GND") (pintype "power_in"))
      (node (ref "LED103") (pin "GND") (pinfunction "GND_GND") (pintype "power_in"))
      (node (ref "LED104") (pin "GND") (pinfunction "GND_GND") (pintype "power_in"))
      (node (ref "LED105") (pin "GND") (pinfunction "GND_GND") (pintype "power_in"))
      (node (ref "LED106") (pin "GND") (pinfunction "GND_GND") (pintype "power_in"))
      (node (ref "LED107") (pin "GND") (pinfunction "GND_GND") (pintype "power_in"))
      (node (ref "LED108") (pin "GND") (pinfunction "GND_GND") (pintype "power_in"))
      (node (ref "LED109") (pin "GND") (pinfunction "GND_GND") (pintype "power_in"))
      (node (ref "LED11") (pin "GND") (pinfunction "GND_GND") (pintype "power_in"))
      (node (ref "LED110") (pin "GND") (pinfunction "GND_GND") (pintype "power_in"))
      (node (ref "LED111") (pin "GND") (pinfunction "GND_GND") (pintype "power_in"))
      (node (ref "LED112") (pin "GND") (pinfunction "GND_GND") (pintype "power_in"))
      (node (ref "LED113") (pin "GND") (pinfunction "GND_GND") (pintype "power_in"))
      (node (ref "LED114") (pin "GND") (pinfunction "GND_GND") (pintype "power_in"))
      (node (ref "LED115") (pin "GND") (pinfunction "GND_GND") (pintype "power_in"))
      (node (ref "LED116") (pin "GND") (pinfunction "GND_GND") (pintype "power_in"))
      (node (ref "LED117") (pin "GND") (pinfunction "GND_GND") (pintype "power_in"))
      (node (ref "LED118") (pin "GND") (pinfunction "GND_GND") (pintype "power_in"))
      (node (ref "LED119") (pin "GND") (pinfunction "GND_GND") (pintype "power_in"))
      (node (ref "LED12") (pin "GND") (pinfunction "GND_GND") (pintype "power_in"))
      (node (ref "LED120") (pin "GND") (pinfunction "GND_GND") (pintype "power_in"))
      (node (ref "LED121") (pin "GND") (pinfunction "GND_GND") (pintype "power_in"))
      (node (ref "LED122") (pin "GND") (pinfunction "GND_GND") (pintype "power_in"))
      (node (ref "LED123") (pin "GND") (pinfunction "GND_GND") (pintype "power_in"))
      (node (ref "LED124") (pin "GND") (pinfunction "GND_GND") (pintype "power_in"))
      (node (ref "LED125") (pin "GND") (pinfunction "GND_GND") (pintype "power_in"))
      (node (ref "LED126") (pin "GND") (pinfunction "GND_GND") (pintype "power_in"))
      (node (ref "LED127") (pin "GND") (pinfunction "GND_GND") (pintype "power_in"))
      (node (ref "LED128") (pin "GND") (pinfunction "GND_GND") (pintype "power_in"))
      (node (ref "LED13") (pin "GND") (pinfunction "GND_GND") (pintype "power_in"))
      (node (ref "LED14") (pin "GND") (pinfunction "GND_GND") (pintype "power_in"))
      (node (ref "LED15") (pin "GND") (pinfunction "GND_GND") (pintype "power_in"))
      (node (ref "LED16") (pin "GND") (pinfunction "GND_GND") (pintype "power_in"))
      (node (ref "LED17") (pin "GND") (pinfunction "GND_GND") (pintype "power_in"))
      (node (ref "LED18") (pin "GND") (pinfunction "GND_GND") (pintype "power_in"))
      (node (ref "LED19") (pin "GND") (pinfunction "GND_GND") (pintype "power_in"))
      (node (ref "LED2") (pin "GND") (pinfunction "GND_GND") (pintype "power_in"))
      (node (ref "LED20") (pin "GND") (pinfunction "GND_GND") (pintype "power_in"))
      (node (ref "LED21") (pin "GND") (pinfunction "GND_GND") (pintype "power_in"))
      (node (ref "LED22") (pin "GND") (pinfunction "GND_GND") (pintype "power_in"))
      (node (ref "LED23") (pin "GND") (pinfunction "GND_GND") (pintype "power_in"))
      (node (ref "LED24") (pin "GND") (pinfunction "GND_GND") (pintype "power_in"))
      (node (ref "LED25") (pin "GND") (pinfunction "GND_GND") (pintype "power_in"))
      (node (ref "LED26") (pin "GND") (pinfunction "GND_GND") (pintype "power_in"))
      (node (ref "LED27") (pin "GND") (pinfunction "GND_GND") (pintype "power_in"))
      (node (ref "LED28") (pin "GND") (pinfunction "GND_GND") (pintype "power_in"))
      (node (ref "LED29") (pin "GND") (pinfunction "GND_GND") (pintype "power_in"))
      (node (ref "LED3") (pin "GND") (pinfunction "GND_GND") (pintype "power_in"))
      (node (ref "LED30") (pin "GND") (pinfunction "GND_GND") (pintype "power_in"))
      (node (ref "LED31") (pin "GND") (pinfunction "GND_GND") (pintype "power_in"))
      (node (ref "LED32") (pin "GND") (pinfunction "GND_GND") (pintype "power_in"))
      (node (ref "LED33") (pin "GND") (pinfunction "GND_GND") (pintype "power_in"))
      (node (ref "LED34") (pin "GND") (pinfunction "GND_GND") (pintype "power_in"))
      (node (ref "LED35") (pin "GND") (pinfunction "GND_GND") (pintype "power_in"))
      (node (ref "LED36") (pin "GND") (pinfunction "GND_GND") (pintype "power_in"))
      (node (ref "LED37") (pin "GND") (pinfunction "GND_GND") (pintype "power_in"))
      (node (ref "LED38") (pin "GND") (pinfunction "GND_GND") (pintype "power_in"))
      (node (ref "LED39") (pin "GND") (pinfunction "GND_GND") (pintype "power_in"))
      (node (ref "LED4") (pin "GND") (pinfunction "GND_GND") (pintype "power_in"))
      (node (ref "LED40") (pin "GND") (pinfunction "GND_GND") (pintype "power_in"))
      (node (ref "LED41") (pin "GND") (pinfunction "GND_GND") (pintype "power_in"))
      (node (ref "LED42") (pin "GND") (pinfunction "GND_GND") (pintype "power_in"))
      (node (ref "LED43") (pin "GND") (pinfunction "GND_GND") (pintype "power_in"))
      (node (ref "LED44") (pin "GND") (pinfunction "GND_GND") (pintype "power_in"))
      (node (ref "LED45") (pin "GND") (pinfunction "GND_GND") (pintype "power_in"))
      (node (ref "LED46") (pin "GND") (pinfunction "GND_GND") (pintype "power_in"))
      (node (ref "LED47") (pin "GND") (pinfunction "GND_GND") (pintype "power_in"))
      (node (ref "LED48") (pin "GND") (pinfunction "GND_GND") (pintype "power_in"))
      (node (ref "LED49") (pin "GND") (pinfunction "GND_GND") (pintype "power_in"))
      (node (ref "LED5") (pin "GND") (pinfunction "GND_GND") (pintype "power_in"))
      (node (ref "LED50") (pin "GND") (pinfunction "GND_GND") (pintype "power_in"))
      (node (ref "LED51") (pin "GND") (pinfunction "GND_GND") (pintype "power_in"))
      (node (ref "LED52") (pin "GND") (pinfunction "GND_GND") (pintype "power_in"))
      (node (ref "LED53") (pin "GND") (pinfunction "GND_GND") (pintype "power_in"))
      (node (ref "LED54") (pin "GND") (pinfunction "GND_GND") (pintype "power_in"))
      (node (ref "LED55") (pin "GND") (pinfunction "GND_GND") (pintype "power_in"))
      (node (ref "LED56") (pin "GND") (pinfunction "GND_GND") (pintype "power_in"))
      (node (ref "LED57") (pin "GND") (pinfunction "GND_GND") (pintype "power_in"))
      (node (ref "LED58") (pin "GND") (pinfunction "GND_GND") (pintype "power_in"))
      (node (ref "LED59") (pin "GND") (pinfunction "GND_GND") (pintype "power_in"))
      (node (ref "LED6") (pin "GND") (pinfunction "GND_GND") (pintype "power_in"))
      (node (ref "LED60") (pin "GND") (pinfunction "GND_GND") (pintype "power_in"))
      (node (ref "LED61") (pin "GND") (pinfunction "GND_GND") (pintype "power_in"))
      (node (ref "LED62") (pin "GND") (pinfunction "GND_GND") (pintype "power_in"))
      (node (ref "LED63") (pin "GND") (pinfunction "GND_GND") (pintype "power_in"))
      (node (ref "LED64") (pin "GND") (pinfunction "GND_GND") (pintype "power_in"))
      (node (ref "LED65") (pin "GND") (pinfunction "GND_GND") (pintype "power_in"))
      (node (ref "LED66") (pin "GND") (pinfunction "GND_GND") (pintype "power_in"))
      (node (ref "LED67") (pin "GND") (pinfunction "GND_GND") (pintype "power_in"))
      (node (ref "LED68") (pin "GND") (pinfunction "GND_GND") (pintype "power_in"))
      (node (ref "LED69") (pin "GND") (pinfunction "GND_GND") (pintype "power_in"))
      (node (ref "LED7") (pin "GND") (pinfunction "GND_GND") (pintype "power_in"))
      (node (ref "LED70") (pin "GND") (pinfunction "GND_GND") (pintype "power_in"))
      (node (ref "LED71") (pin "GND") (pinfunction "GND_GND") (pintype "power_in"))
      (node (ref "LED72") (pin "GND") (pinfunction "GND_GND") (pintype "power_in"))
      (node (ref "LED73") (pin "GND") (pinfunction "GND_GND") (pintype "power_in"))
      (node (ref "LED74") (pin "GND") (pinfunction "GND_GND") (pintype "power_in"))
      (node (ref "LED75") (pin "GND") (pinfunction "GND_GND") (pintype "power_in"))
      (node (ref "LED76") (pin "GND") (pinfunction "GND_GND") (pintype "power_in"))
      (node (ref "LED77") (pin "GND") (pinfunction "GND_GND") (pintype "power_in"))
      (node (ref "LED78") (pin "GND") (pinfunction "GND_GND") (pintype "power_in"))
      (node (ref "LED79") (pin "GND") (pinfunction "GND_GND") (pintype "power_in"))
      (node (ref "LED8") (pin "GND") (pinfunction "GND_GND") (pintype "power_in"))
      (node (ref "LED80") (pin "GND") (pinfunction "GND_GND") (pintype "power_in"))
      (node (ref "LED81") (pin "GND") (pinfunction "GND_GND") (pintype "power_in"))
      (node (ref "LED82") (pin "GND") (pinfunction "GND_GND") (pintype "power_in"))
      (node (ref "LED83") (pin "GND") (pinfunction "GND_GND") (pintype "power_in"))
      (node (ref "LED84") (pin "GND") (pinfunction "GND_GND") (pintype "power_in"))
      (node (ref "LED85") (pin "GND") (pinfunction "GND_GND") (pintype "power_in"))
      (node (ref "LED86") (pin "GND") (pinfunction "GND_GND") (pintype "power_in"))
      (node (ref "LED87") (pin "GND") (pinfunction "GND_GND") (pintype "power_in"))
      (node (ref "LED88") (pin "GND") (pinfunction "GND_GND") (pintype "power_in"))
      (node (ref "LED89") (pin "GND") (pinfunction "GND_GND") (pintype "power_in"))
      (node (ref "LED9") (pin "GND") (pinfunction "GND_GND") (pintype "power_in"))
      (node (ref "LED90") (pin "GND") (pinfunction "GND_GND") (pintype "power_in"))
      (node (ref "LED91") (pin "GND") (pinfunction "GND_GND") (pintype "power_in"))
      (node (ref "LED92") (pin "GND") (pinfunction "GND_GND") (pintype "power_in"))
      (node (ref "LED93") (pin "GND") (pinfunction "GND_GND") (pintype "power_in"))
      (node (ref "LED94") (pin "GND") (pinfunction "GND_GND") (pintype "power_in"))
      (node (ref "LED95") (pin "GND") (pinfunction "GND_GND") (pintype "power_in"))
      (node (ref "LED96") (pin "GND") (pinfunction "GND_GND") (pintype "power_in"))
      (node (ref "LED97") (pin "GND") (pinfunction "GND_GND") (pintype "power_in"))
      (node (ref "LED98") (pin "GND") (pinfunction "GND_GND") (pintype "power_in"))
      (node (ref "LED99") (pin "GND") (pinfunction "GND_GND") (pintype "power_in"))
    )
    (net (code "4") (name "Net-(LED1-PadDOUT)") (class "Default")
      (node (ref "LED1") (pin "DOUT") (pinfunction "DOUT_DOUT") (pintype "bidirectional"))
      (node (ref "LED2") (pin "DIN") (pinfunction "DIN_DIN") (pintype "bidirectional"))
    )
    (net (code "5") (name "Net-(LED2-PadDOUT)") (class "Default")
      (node (ref "LED2") (pin "DOUT") (pinfunction "DOUT_DOUT") (pintype "bidirectional"))
      (node (ref "LED3") (pin "DIN") (pinfunction "DIN_DIN") (pintype "bidirectional"))
    )
    (net (code "6") (name "Net-(LED3-PadDOUT)") (class "Default")
      (node (ref "LED3") (pin "DOUT") (pinfunction "DOUT_DOUT") (pintype "bidirectional"))
      (node (ref "LED4") (pin "DIN") (pinfunction "DIN_DIN") (pintype "bidirectional"))
    )
    (net (code "7") (name "Net-(LED4-PadDOUT)") (class "Default")
      (node (ref "LED4") (pin "DOUT") (pinfunction "DOUT_DOUT") (pintype "bidirectional"))
      (node (ref "LED5") (pin "DIN") (pinfunction "DIN_DIN") (pintype "bidirectional"))
    )
    (net (code "8") (name "Net-(LED5-PadDOUT)") (class "Default")
      (node (ref "LED5") (pin "DOUT") (pinfunction "DOUT_DOUT") (pintype "bidirectional"))
      (node (ref "LED6") (pin "DIN") (pinfunction "DIN_DIN") (pintype "bidirectional"))
    )
    (net (code "9") (name "Net-(LED6-PadDOUT)") (class "Default")
      (node (ref "LED6") (pin "DOUT") (pinfunction "DOUT_DOUT") (pintype "bidirectional"))
      (node (ref "LED7") (pin "DIN") (pinfunction "DIN_DIN") (pintype "bidirectional"))
    )
    (net (code "10") (name "Net-(LED7-PadDOUT)") (class "Default")
      (node (ref "LED7") (pin "DOUT") (pinfunction "DOUT_DOUT") (pintype "bidirectional"))
      (node (ref "LED8") (pin "DIN") (pinfunction "DIN_DIN") (pintype "bidirectional"))
    )
    (net (code "11") (name "Net-(LED8-PadDOUT)") (class "Default")
      (node (ref "LED8") (pin "DOUT") (pinfunction "DOUT_DOUT") (pintype "bidirectional"))
      (node (ref "LED9") (pin "DIN") (pinfunction "DIN_DIN") (pintype "bidirectional"))
    )
    (net (code "12") (name "Net-(LED10-PadDIN)") (class "Default")
      (node (ref "LED10") (pin "DIN") (pinfunction "DIN_DIN") (pintype "bidirectional"))
      (node (ref "LED9") (pin "DOUT") (pinfunction "DOUT_DOUT") (pintype "bidirectional"))
    )
    (net (code "13") (name "Net-(LED10-PadDOUT)") (class "Default")
      (node (ref "LED10") (pin "DOUT") (pinfunction "DOUT_DOUT") (pintype "bidirectional"))
      (node (ref "LED11") (pin "DIN") (pinfunction "DIN_DIN") (pintype "bidirectional"))
    )
    (net (code "14") (name "Net-(LED11-PadDOUT)") (class "Default")
      (node (ref "LED11") (pin "DOUT") (pinfunction "DOUT_DOUT") (pintype "bidirectional"))
      (node (ref "LED12") (pin "DIN") (pinfunction "DIN_DIN") (pintype "bidirectional"))
    )
    (net (code "15") (name "Net-(LED12-PadDOUT)") (class "Default")
      (node (ref "LED12") (pin "DOUT") (pinfunction "DOUT_DOUT") (pintype "bidirectional"))
      (node (ref "LED13") (pin "DIN") (pinfunction "DIN_DIN") (pintype "bidirectional"))
    )
    (net (code "16") (name "Net-(LED13-PadDOUT)") (class "Default")
      (node (ref "LED13") (pin "DOUT") (pinfunction "DOUT_DOUT") (pintype "bidirectional"))
      (node (ref "LED14") (pin "DIN") (pinfunction "DIN_DIN") (pintype "bidirectional"))
    )
    (net (code "17") (name "Net-(LED14-PadDOUT)") (class "Default")
      (node (ref "LED14") (pin "DOUT") (pinfunction "DOUT_DOUT") (pintype "bidirectional"))
      (node (ref "LED15") (pin "DIN") (pinfunction "DIN_DIN") (pintype "bidirectional"))
    )
    (net (code "18") (name "Net-(LED15-PadDOUT)") (class "Default")
      (node (ref "LED15") (pin "DOUT") (pinfunction "DOUT_DOUT") (pintype "bidirectional"))
      (node (ref "LED16") (pin "DIN") (pinfunction "DIN_DIN") (pintype "bidirectional"))
    )
    (net (code "19") (name "Net-(LED16-PadDOUT)") (class "Default")
      (node (ref "LED16") (pin "DOUT") (pinfunction "DOUT_DOUT") (pintype "bidirectional"))
      (node (ref "LED17") (pin "DIN") (pinfunction "DIN_DIN") (pintype "bidirectional"))
    )
    (net (code "20") (name "Net-(LED17-PadDOUT)") (class "Default")
      (node (ref "LED17") (pin "DOUT") (pinfunction "DOUT_DOUT") (pintype "bidirectional"))
      (node (ref "LED18") (pin "DIN") (pinfunction "DIN_DIN") (pintype "bidirectional"))
    )
    (net (code "21") (name "Net-(LED18-PadDOUT)") (class "Default")
      (node (ref "LED18") (pin "DOUT") (pinfunction "DOUT_DOUT") (pintype "bidirectional"))
      (node (ref "LED19") (pin "DIN") (pinfunction "DIN_DIN") (pintype "bidirectional"))
    )
    (net (code "22") (name "Net-(LED19-PadDOUT)") (class "Default")
      (node (ref "LED19") (pin "DOUT") (pinfunction "DOUT_DOUT") (pintype "bidirectional"))
      (node (ref "LED20") (pin "DIN") (pinfunction "DIN_DIN") (pintype "bidirectional"))
    )
    (net (code "23") (name "Net-(LED20-PadDOUT)") (class "Default")
      (node (ref "LED20") (pin "DOUT") (pinfunction "DOUT_DOUT") (pintype "bidirectional"))
      (node (ref "LED21") (pin "DIN") (pinfunction "DIN_DIN") (pintype "bidirectional"))
    )
    (net (code "24") (name "Net-(LED21-PadDOUT)") (class "Default")
      (node (ref "LED21") (pin "DOUT") (pinfunction "DOUT_DOUT") (pintype "bidirectional"))
      (node (ref "LED22") (pin "DIN") (pinfunction "DIN_DIN") (pintype "bidirectional"))
    )
    (net (code "25") (name "Net-(LED22-PadDOUT)") (class "Default")
      (node (ref "LED22") (pin "DOUT") (pinfunction "DOUT_DOUT") (pintype "bidirectional"))
      (node (ref "LED23") (pin "DIN") (pinfunction "DIN_DIN") (pintype "bidirectional"))
    )
    (net (code "26") (name "Net-(LED23-PadDOUT)") (class "Default")
      (node (ref "LED23") (pin "DOUT") (pinfunction "DOUT_DOUT") (pintype "bidirectional"))
      (node (ref "LED24") (pin "DIN") (pinfunction "DIN_DIN") (pintype "bidirectional"))
    )
    (net (code "27") (name "Net-(LED24-PadDOUT)") (class "Default")
      (node (ref "LED24") (pin "DOUT") (pinfunction "DOUT_DOUT") (pintype "bidirectional"))
      (node (ref "LED25") (pin "DIN") (pinfunction "DIN_DIN") (pintype "bidirectional"))
    )
    (net (code "28") (name "Net-(LED25-PadDOUT)") (class "Default")
      (node (ref "LED25") (pin "DOUT") (pinfunction "DOUT_DOUT") (pintype "bidirectional"))
      (node (ref "LED26") (pin "DIN") (pinfunction "DIN_DIN") (pintype "bidirectional"))
    )
    (net (code "29") (name "Net-(LED26-PadDOUT)") (class "Default")
      (node (ref "LED26") (pin "DOUT") (pinfunction "DOUT_DOUT") (pintype "bidirectional"))
      (node (ref "LED27") (pin "DIN") (pinfunction "DIN_DIN") (pintype "bidirectional"))
    )
    (net (code "30") (name "Net-(LED27-PadDOUT)") (class "Default")
      (node (ref "LED27") (pin "DOUT") (pinfunction "DOUT_DOUT") (pintype "bidirectional"))
      (node (ref "LED28") (pin "DIN") (pinfunction "DIN_DIN") (pintype "bidirectional"))
    )
    (net (code "31") (name "Net-(LED28-PadDOUT)") (class "Default")
      (node (ref "LED28") (pin "DOUT") (pinfunction "DOUT_DOUT") (pintype "bidirectional"))
      (node (ref "LED29") (pin "DIN") (pinfunction "DIN_DIN") (pintype "bidirectional"))
    )
    (net (code "32") (name "Net-(LED29-PadDOUT)") (class "Default")
      (node (ref "LED29") (pin "DOUT") (pinfunction "DOUT_DOUT") (pintype "bidirectional"))
      (node (ref "LED30") (pin "DIN") (pinfunction "DIN_DIN") (pintype "bidirectional"))
    )
    (net (code "33") (name "Net-(LED30-PadDOUT)") (class "Default")
      (node (ref "LED30") (pin "DOUT") (pinfunction "DOUT_DOUT") (pintype "bidirectional"))
      (node (ref "LED31") (pin "DIN") (pinfunction "DIN_DIN") (pintype "bidirectional"))
    )
    (net (code "34") (name "Net-(LED31-PadDOUT)") (class "Default")
      (node (ref "LED31") (pin "DOUT") (pinfunction "DOUT_DOUT") (pintype "bidirectional"))
      (node (ref "LED32") (pin "DIN") (pinfunction "DIN_DIN") (pintype "bidirectional"))
    )
    (net (code "35") (name "Net-(LED32-PadDOUT)") (class "Default")
      (node (ref "LED32") (pin "DOUT") (pinfunction "DOUT_DOUT") (pintype "bidirectional"))
      (node (ref "LED33") (pin "DIN") (pinfunction "DIN_DIN") (pintype "bidirectional"))
    )
    (net (code "36") (name "Net-(LED33-PadDOUT)") (class "Default")
      (node (ref "LED33") (pin "DOUT") (pinfunction "DOUT_DOUT") (pintype "bidirectional"))
      (node (ref "LED34") (pin "DIN") (pinfunction "DIN_DIN") (pintype "bidirectional"))
    )
    (net (code "37") (name "Net-(LED34-PadDOUT)") (class "Default")
      (node (ref "LED34") (pin "DOUT") (pinfunction "DOUT_DOUT") (pintype "bidirectional"))
      (node (ref "LED35") (pin "DIN") (pinfunction "DIN_DIN") (pintype "bidirectional"))
    )
    (net (code "38") (name "Net-(LED35-PadDOUT)") (class "Default")
      (node (ref "LED35") (pin "DOUT") (pinfunction "DOUT_DOUT") (pintype "bidirectional"))
      (node (ref "LED36") (pin "DIN") (pinfunction "DIN_DIN") (pintype "bidirectional"))
    )
    (net (code "39") (name "Net-(LED36-PadDOUT)") (class "Default")
      (node (ref "LED36") (pin "DOUT") (pinfunction "DOUT_DOUT") (pintype "bidirectional"))
      (node (ref "LED37") (pin "DIN") (pinfunction "DIN_DIN") (pintype "bidirectional"))
    )
    (net (code "40") (name "Net-(LED37-PadDOUT)") (class "Default")
      (node (ref "LED37") (pin "DOUT") (pinfunction "DOUT_DOUT") (pintype "bidirectional"))
      (node (ref "LED38") (pin "DIN") (pinfunction "DIN_DIN") (pintype "bidirectional"))
    )
    (net (code "41") (name "Net-(LED38-PadDOUT)") (class "Default")
      (node (ref "LED38") (pin "DOUT") (pinfunction "DOUT_DOUT") (pintype "bidirectional"))
      (node (ref "LED39") (pin "DIN") (pinfunction "DIN_DIN") (pintype "bidirectional"))
    )
    (net (code "42") (name "Net-(LED39-PadDOUT)") (class "Default")
      (node (ref "LED39") (pin "DOUT") (pinfunction "DOUT_DOUT") (pintype "bidirectional"))
      (node (ref "LED40") (pin "DIN") (pinfunction "DIN_DIN") (pintype "bidirectional"))
    )
    (net (code "43") (name "Net-(LED40-PadDOUT)") (class "Default")
      (node (ref "LED40") (pin "DOUT") (pinfunction "DOUT_DOUT") (pintype "bidirectional"))
      (node (ref "LED41") (pin "DIN") (pinfunction "DIN_DIN") (pintype "bidirectional"))
    )
    (net (code "44") (name "Net-(LED41-PadDOUT)") (class "Default")
      (node (ref "LED41") (pin "DOUT") (pinfunction "DOUT_DOUT") (pintype "bidirectional"))
      (node (ref "LED42") (pin "DIN") (pinfunction "DIN_DIN") (pintype "bidirectional"))
    )
    (net (code "45") (name "Net-(LED42-PadDOUT)") (class "Default")
      (node (ref "LED42") (pin "DOUT") (pinfunction "DOUT_DOUT") (pintype "bidirectional"))
      (node (ref "LED43") (pin "DIN") (pinfunction "DIN_DIN") (pintype "bidirectional"))
    )
    (net (code "46") (name "Net-(LED43-PadDOUT)") (class "Default")
      (node (ref "LED43") (pin "DOUT") (pinfunction "DOUT_DOUT") (pintype "bidirectional"))
      (node (ref "LED44") (pin "DIN") (pinfunction "DIN_DIN") (pintype "bidirectional"))
    )
    (net (code "47") (name "Net-(LED44-PadDOUT)") (class "Default")
      (node (ref "LED44") (pin "DOUT") (pinfunction "DOUT_DOUT") (pintype "bidirectional"))
      (node (ref "LED45") (pin "DIN") (pinfunction "DIN_DIN") (pintype "bidirectional"))
    )
    (net (code "48") (name "Net-(LED45-PadDOUT)") (class "Default")
      (node (ref "LED45") (pin "DOUT") (pinfunction "DOUT_DOUT") (pintype "bidirectional"))
      (node (ref "LED46") (pin "DIN") (pinfunction "DIN_DIN") (pintype "bidirectional"))
    )
    (net (code "49") (name "Net-(LED46-PadDOUT)") (class "Default")
      (node (ref "LED46") (pin "DOUT") (pinfunction "DOUT_DOUT") (pintype "bidirectional"))
      (node (ref "LED47") (pin "DIN") (pinfunction "DIN_DIN") (pintype "bidirectional"))
    )
    (net (code "50") (name "Net-(LED47-PadDOUT)") (class "Default")
      (node (ref "LED47") (pin "DOUT") (pinfunction "DOUT_DOUT") (pintype "bidirectional"))
      (node (ref "LED48") (pin "DIN") (pinfunction "DIN_DIN") (pintype "bidirectional"))
    )
    (net (code "51") (name "Net-(LED48-PadDOUT)") (class "Default")
      (node (ref "LED48") (pin "DOUT") (pinfunction "DOUT_DOUT") (pintype "bidirectional"))
      (node (ref "LED49") (pin "DIN") (pinfunction "DIN_DIN") (pintype "bidirectional"))
    )
    (net (code "52") (name "Net-(LED49-PadDOUT)") (class "Default")
      (node (ref "LED49") (pin "DOUT") (pinfunction "DOUT_DOUT") (pintype "bidirectional"))
      (node (ref "LED50") (pin "DIN") (pinfunction "DIN_DIN") (pintype "bidirectional"))
    )
    (net (code "53") (name "Net-(LED50-PadDOUT)") (class "Default")
      (node (ref "LED50") (pin "DOUT") (pinfunction "DOUT_DOUT") (pintype "bidirectional"))
      (node (ref "LED51") (pin "DIN") (pinfunction "DIN_DIN") (pintype "bidirectional"))
    )
    (net (code "54") (name "Net-(LED51-PadDOUT)") (class "Default")
      (node (ref "LED51") (pin "DOUT") (pinfunction "DOUT_DOUT") (pintype "bidirectional"))
      (node (ref "LED52") (pin "DIN") (pinfunction "DIN_DIN") (pintype "bidirectional"))
    )
    (net (code "55") (name "Net-(LED52-PadDOUT)") (class "Default")
      (node (ref "LED52") (pin "DOUT") (pinfunction "DOUT_DOUT") (pintype "bidirectional"))
      (node (ref "LED53") (pin "DIN") (pinfunction "DIN_DIN") (pintype "bidirectional"))
    )
    (net (code "56") (name "Net-(LED53-PadDOUT)") (class "Default")
      (node (ref "LED53") (pin "DOUT") (pinfunction "DOUT_DOUT") (pintype "bidirectional"))
      (node (ref "LED54") (pin "DIN") (pinfunction "DIN_DIN") (pintype "bidirectional"))
    )
    (net (code "57") (name "Net-(LED54-PadDOUT)") (class "Default")
      (node (ref "LED54") (pin "DOUT") (pinfunction "DOUT_DOUT") (pintype "bidirectional"))
      (node (ref "LED55") (pin "DIN") (pinfunction "DIN_DIN") (pintype "bidirectional"))
    )
    (net (code "58") (name "Net-(LED55-PadDOUT)") (class "Default")
      (node (ref "LED55") (pin "DOUT") (pinfunction "DOUT_DOUT") (pintype "bidirectional"))
      (node (ref "LED56") (pin "DIN") (pinfunction "DIN_DIN") (pintype "bidirectional"))
    )
    (net (code "59") (name "Net-(LED56-PadDOUT)") (class "Default")
      (node (ref "LED56") (pin "DOUT") (pinfunction "DOUT_DOUT") (pintype "bidirectional"))
      (node (ref "LED57") (pin "DIN") (pinfunction "DIN_DIN") (pintype "bidirectional"))
    )
    (net (code "60") (name "Net-(LED57-PadDOUT)") (class "Default")
      (node (ref "LED57") (pin "DOUT") (pinfunction "DOUT_DOUT") (pintype "bidirectional"))
      (node (ref "LED58") (pin "DIN") (pinfunction "DIN_DIN") (pintype "bidirectional"))
    )
    (net (code "61") (name "Net-(LED58-PadDOUT)") (class "Default")
      (node (ref "LED58") (pin "DOUT") (pinfunction "DOUT_DOUT") (pintype "bidirectional"))
      (node (ref "LED59") (pin "DIN") (pinfunction "DIN_DIN") (pintype "bidirectional"))
    )
    (net (code "62") (name "Net-(LED59-PadDOUT)") (class "Default")
      (node (ref "LED59") (pin "DOUT") (pinfunction "DOUT_DOUT") (pintype "bidirectional"))
      (node (ref "LED60") (pin "DIN") (pinfunction "DIN_DIN") (pintype "bidirectional"))
    )
    (net (code "63") (name "Net-(LED60-PadDOUT)") (class "Default")
      (node (ref "LED60") (pin "DOUT") (pinfunction "DOUT_DOUT") (pintype "bidirectional"))
      (node (ref "LED61") (pin "DIN") (pinfunction "DIN_DIN") (pintype "bidirectional"))
    )
    (net (code "64") (name "Net-(LED61-PadDOUT)") (class "Default")
      (node (ref "LED61") (pin "DOUT") (pinfunction "DOUT_DOUT") (pintype "bidirectional"))
      (node (ref "LED62") (pin "DIN") (pinfunction "DIN_DIN") (pintype "bidirectional"))
    )
    (net (code "65") (name "Net-(LED62-PadDOUT)") (class "Default")
      (node (ref "LED62") (pin "DOUT") (pinfunction "DOUT_DOUT") (pintype "bidirectional"))
      (node (ref "LED63") (pin "DIN") (pinfunction "DIN_DIN") (pintype "bidirectional"))
    )
    (net (code "66") (name "Net-(LED63-PadDOUT)") (class "Default")
      (node (ref "LED63") (pin "DOUT") (pinfunction "DOUT_DOUT") (pintype "bidirectional"))
      (node (ref "LED64") (pin "DIN") (pinfunction "DIN_DIN") (pintype "bidirectional"))
    )
    (net (code "67") (name "Net-(LED64-PadDOUT)") (class "Default")
      (node (ref "LED64") (pin "DOUT") (pinfunction "DOUT_DOUT") (pintype "bidirectional"))
      (node (ref "LED65") (pin "DIN") (pinfunction "DIN_DIN") (pintype "bidirectional"))
    )
    (net (code "68") (name "Net-(LED65-PadDOUT)") (class "Default")
      (node (ref "LED65") (pin "DOUT") (pinfunction "DOUT_DOUT") (pintype "bidirectional"))
      (node (ref "LED66") (pin "DIN") (pinfunction "DIN_DIN") (pintype "bidirectional"))
    )
    (net (code "69") (name "Net-(LED66-PadDOUT)") (class "Default")
      (node (ref "LED66") (pin "DOUT") (pinfunction "DOUT_DOUT") (pintype "bidirectional"))
      (node (ref "LED67") (pin "DIN") (pinfunction "DIN_DIN") (pintype "bidirectional"))
    )
    (net (code "70") (name "Net-(LED67-PadDOUT)") (class "Default")
      (node (ref "LED67") (pin "DOUT") (pinfunction "DOUT_DOUT") (pintype "bidirectional"))
      (node (ref "LED68") (pin "DIN") (pinfunction "DIN_DIN") (pintype "bidirectional"))
    )
    (net (code "71") (name "Net-(LED68-PadDOUT)") (class "Default")
      (node (ref "LED68") (pin "DOUT") (pinfunction "DOUT_DOUT") (pintype "bidirectional"))
      (node (ref "LED69") (pin "DIN") (pinfunction "DIN_DIN") (pintype "bidirectional"))
    )
    (net (code "72") (name "Net-(LED69-PadDOUT)") (class "Default")
      (node (ref "LED69") (pin "DOUT") (pinfunction "DOUT_DOUT") (pintype "bidirectional"))
      (node (ref "LED70") (pin "DIN") (pinfunction "DIN_DIN") (pintype "bidirectional"))
    )
    (net (code "73") (name "Net-(LED70-PadDOUT)") (class "Default")
      (node (ref "LED70") (pin "DOUT") (pinfunction "DOUT_DOUT") (pintype "bidirectional"))
      (node (ref "LED71") (pin "DIN") (pinfunction "DIN_DIN") (pintype "bidirectional"))
    )
    (net (code "74") (name "Net-(LED71-PadDOUT)") (class "Default")
      (node (ref "LED71") (pin "DOUT") (pinfunction "DOUT_DOUT") (pintype "bidirectional"))
      (node (ref "LED72") (pin "DIN") (pinfunction "DIN_DIN") (pintype "bidirectional"))
    )
    (net (code "75") (name "Net-(LED72-PadDOUT)") (class "Default")
      (node (ref "LED72") (pin "DOUT") (pinfunction "DOUT_DOUT") (pintype "bidirectional"))
      (node (ref "LED73") (pin "DIN") (pinfunction "DIN_DIN") (pintype "bidirectional"))
    )
    (net (code "76") (name "Net-(LED73-PadDOUT)") (class "Default")
      (node (ref "LED73") (pin "DOUT") (pinfunction "DOUT_DOUT") (pintype "bidirectional"))
      (node (ref "LED74") (pin "DIN") (pinfunction "DIN_DIN") (pintype "bidirectional"))
    )
    (net (code "77") (name "Net-(LED74-PadDOUT)") (class "Default")
      (node (ref "LED74") (pin "DOUT") (pinfunction "DOUT_DOUT") (pintype "bidirectional"))
      (node (ref "LED75") (pin "DIN") (pinfunction "DIN_DIN") (pintype "bidirectional"))
    )
    (net (code "78") (name "Net-(LED75-PadDOUT)") (class "Default")
      (node (ref "LED75") (pin "DOUT") (pinfunction "DOUT_DOUT") (pintype "bidirectional"))
      (node (ref "LED76") (pin "DIN") (pinfunction "DIN_DIN") (pintype "bidirectional"))
    )
    (net (code "79") (name "Net-(LED76-PadDOUT)") (class "Default")
      (node (ref "LED76") (pin "DOUT") (pinfunction "DOUT_DOUT") (pintype "bidirectional"))
      (node (ref "LED77") (pin "DIN") (pinfunction "DIN_DIN") (pintype "bidirectional"))
    )
    (net (code "80") (name "Net-(LED77-PadDOUT)") (class "Default")
      (node (ref "LED77") (pin "DOUT") (pinfunction "DOUT_DOUT") (pintype "bidirectional"))
      (node (ref "LED78") (pin "DIN") (pinfunction "DIN_DIN") (pintype "bidirectional"))
    )
    (net (code "81") (name "Net-(LED78-PadDOUT)") (class "Default")
      (node (ref "LED78") (pin "DOUT") (pinfunction "DOUT_DOUT") (pintype "bidirectional"))
      (node (ref "LED79") (pin "DIN") (pinfunction "DIN_DIN") (pintype "bidirectional"))
    )
    (net (code "82") (name "Net-(LED79-PadDOUT)") (class "Default")
      (node (ref "LED79") (pin "DOUT") (pinfunction "DOUT_DOUT") (pintype "bidirectional"))
      (node (ref "LED80") (pin "DIN") (pinfunction "DIN_DIN") (pintype "bidirectional"))
    )
    (net (code "83") (name "Net-(LED80-PadDOUT)") (class "Default")
      (node (ref "LED80") (pin "DOUT") (pinfunction "DOUT_DOUT") (pintype "bidirectional"))
      (node (ref "LED81") (pin "DIN") (pinfunction "DIN_DIN") (pintype "bidirectional"))
    )
    (net (code "84") (name "Net-(LED81-PadDOUT)") (class "Default")
      (node (ref "LED81") (pin "DOUT") (pinfunction "DOUT_DOUT") (pintype "bidirectional"))
      (node (ref "LED82") (pin "DIN") (pinfunction "DIN_DIN") (pintype "bidirectional"))
    )
    (net (code "85") (name "Net-(LED82-PadDOUT)") (class "Default")
      (node (ref "LED82") (pin "DOUT") (pinfunction "DOUT_DOUT") (pintype "bidirectional"))
      (node (ref "LED83") (pin "DIN") (pinfunction "DIN_DIN") (pintype "bidirectional"))
    )
    (net (code "86") (name "Net-(LED83-PadDOUT)") (class "Default")
      (node (ref "LED83") (pin "DOUT") (pinfunction "DOUT_DOUT") (pintype "bidirectional"))
      (node (ref "LED84") (pin "DIN") (pinfunction "DIN_DIN") (pintype "bidirectional"))
    )
    (net (code "87") (name "Net-(LED84-PadDOUT)") (class "Default")
      (node (ref "LED84") (pin "DOUT") (pinfunction "DOUT_DOUT") (pintype "bidirectional"))
      (node (ref "LED85") (pin "DIN") (pinfunction "DIN_DIN") (pintype "bidirectional"))
    )
    (net (code "88") (name "Net-(LED85-PadDOUT)") (class "Default")
      (node (ref "LED85") (pin "DOUT") (pinfunction "DOUT_DOUT") (pintype "bidirectional"))
      (node (ref "LED86") (pin "DIN") (pinfunction "DIN_DIN") (pintype "bidirectional"))
    )
    (net (code "89") (name "Net-(LED86-PadDOUT)") (class "Default")
      (node (ref "LED86") (pin "DOUT") (pinfunction "DOUT_DOUT") (pintype "bidirectional"))
      (node (ref "LED87") (pin "DIN") (pinfunction "DIN_DIN") (pintype "bidirectional"))
    )
    (net (code "90") (name "Net-(LED87-PadDOUT)") (class "Default")
      (node (ref "LED87") (pin "DOUT") (pinfunction "DOUT_DOUT") (pintype "bidirectional"))
      (node (ref "LED88") (pin "DIN") (pinfunction "DIN_DIN") (pintype "bidirectional"))
    )
    (net (code "91") (name "Net-(LED88-PadDOUT)") (class "Default")
      (node (ref "LED88") (pin "DOUT") (pinfunction "DOUT_DOUT") (pintype "bidirectional"))
      (node (ref "LED89") (pin "DIN") (pinfunction "DIN_DIN") (pintype "bidirectional"))
    )
    (net (code "92") (name "Net-(LED89-PadDOUT)") (class "Default")
      (node (ref "LED89") (pin "DOUT") (pinfunction "DOUT_DOUT") (pintype "bidirectional"))
      (node (ref "LED90") (pin "DIN") (pinfunction "DIN_DIN") (pintype "bidirectional"))
    )
    (net (code "93") (name "Net-(LED90-PadDOUT)") (class "Default")
      (node (ref "LED90") (pin "DOUT") (pinfunction "DOUT_DOUT") (pintype "bidirectional"))
      (node (ref "LED91") (pin "DIN") (pinfunction "DIN_DIN") (pintype "bidirectional"))
    )
    (net (code "94") (name "Net-(LED91-PadDOUT)") (class "Default")
      (node (ref "LED91") (pin "DOUT") (pinfunction "DOUT_DOUT") (pintype "bidirectional"))
      (node (ref "LED92") (pin "DIN") (pinfunction "DIN_DIN") (pintype "bidirectional"))
    )
    (net (code "95") (name "Net-(LED92-PadDOUT)") (class "Default")
      (node (ref "LED92") (pin "DOUT") (pinfunction "DOUT_DOUT") (pintype "bidirectional"))
      (node (ref "LED93") (pin "DIN") (pinfunction "DIN_DIN") (pintype "bidirectional"))
    )
    (net (code "96") (name "Net-(LED93-PadDOUT)") (class "Default")
      (node (ref "LED93") (pin "DOUT") (pinfunction "DOUT_DOUT") (pintype "bidirectional"))
      (node (ref "LED94") (pin "DIN") (pinfunction "DIN_DIN") (pintype "bidirectional"))
    )
    (net (code "97") (name "Net-(LED94-PadDOUT)") (class "Default")
      (node (ref "LED94") (pin "DOUT") (pinfunction "DOUT_DOUT") (pintype "bidirectional"))
      (node (ref "LED95") (pin "DIN") (pinfunction "DIN_DIN") (pintype "bidirectional"))
    )
    (net (code "98") (name "Net-(LED95-PadDOUT)") (class "Default")
      (node (ref "LED95") (pin "DOUT") (pinfunction "DOUT_DOUT") (pintype "bidirectional"))
      (node (ref "LED96") (pin "DIN") (pinfunction "DIN_DIN") (pintype "bidirectional"))
    )
    (net (code "99") (name "Net-(LED96-PadDOUT)") (class "Default")
      (node (ref "LED96") (pin "DOUT") (pinfunction "DOUT_DOUT") (pintype "bidirectional"))
      (node (ref "LED97") (pin "DIN") (pinfunction "DIN_DIN") (pintype "bidirectional"))
    )
    (net (code "100") (name "Net-(LED97-PadDOUT)") (class "Default")
      (node (ref "LED97") (pin "DOUT") (pinfunction "DOUT_DOUT") (pintype "bidirectional"))
      (node (ref "LED98") (pin "DIN") (pinfunction "DIN_DIN") (pintype "bidirectional"))
    )
    (net (code "101") (name "Net-(LED98-PadDOUT)") (class "Default")
      (node (ref "LED98") (pin "DOUT") (pinfunction "DOUT_DOUT") (pintype "bidirectional"))
      (node (ref "LED99") (pin "DIN") (pinfunction "DIN_DIN") (pintype "bidirectional"))
    )
    (net (code "102") (name "Net-(LED100-PadDIN)") (class "Default")
      (node (ref "LED100") (pin "DIN") (pinfunction "DIN_DIN") (pintype "bidirectional"))
      (node (ref "LED99") (pin "DOUT") (pinfunction "DOUT_DOUT") (pintype "bidirectional"))
    )
    (net (code "103") (name "Net-(LED100-PadDOUT)") (class "Default")
      (node (ref "LED100") (pin "DOUT") (pinfunction "DOUT_DOUT") (pintype "bidirectional"))
      (node (ref "LED101") (pin "DIN") (pinfunction "DIN_DIN") (pintype "bidirectional"))
    )
    (net (code "104") (name "Net-(LED101-PadDOUT)") (class "Default")
      (node (ref "LED101") (pin "DOUT") (pinfunction "DOUT_DOUT") (pintype "bidirectional"))
      (node (ref "LED102") (pin "DIN") (pinfunction "DIN_DIN") (pintype "bidirectional"))
    )
    (net (code "105") (name "Net-(LED102-PadDOUT)") (class "Default")
      (node (ref "LED102") (pin "DOUT") (pinfunction "DOUT_DOUT") (pintype "bidirectional"))
      (node (ref "LED103") (pin "DIN") (pinfunction "DIN_DIN") (pintype "bidirectional"))
    )
    (net (code "106") (name "Net-(LED103-PadDOUT)") (class "Default")
      (node (ref "LED103") (pin "DOUT") (pinfunction "DOUT_DOUT") (pintype "bidirectional"))
      (node (ref "LED104") (pin "DIN") (pinfunction "DIN_DIN") (pintype "bidirectional"))
    )
    (net (code "107") (name "Net-(LED104-PadDOUT)") (class "Default")
      (node (ref "LED104") (pin "DOUT") (pinfunction "DOUT_DOUT") (pintype "bidirectional"))
      (node (ref "LED105") (pin "DIN") (pinfunction "DIN_DIN") (pintype "bidirectional"))
    )
    (net (code "108") (name "Net-(LED105-PadDOUT)") (class "Default")
      (node (ref "LED105") (pin "DOUT") (pinfunction "DOUT_DOUT") (pintype "bidirectional"))
      (node (ref "LED106") (pin "DIN") (pinfunction "DIN_DIN") (pintype "bidirectional"))
    )
    (net (code "109") (name "Net-(LED106-PadDOUT)") (class "Default")
      (node (ref "LED106") (pin "DOUT") (pinfunction "DOUT_DOUT") (pintype "bidirectional"))
      (node (ref "LED107") (pin "DIN") (pinfunction "DIN_DIN") (pintype "bidirectional"))
    )
    (net (code "110") (name "Net-(LED107-PadDOUT)") (class "Default")
      (node (ref "LED107") (pin "DOUT") (pinfunction "DOUT_DOUT") (pintype "bidirectional"))
      (node (ref "LED108") (pin "DIN") (pinfunction "DIN_DIN") (pintype "bidirectional"))
    )
    (net (code "111") (name "Net-(LED108-PadDOUT)") (class "Default")
      (node (ref "LED108") (pin "DOUT") (pinfunction "DOUT_DOUT") (pintype "bidirectional"))
      (node (ref "LED109") (pin "DIN") (pinfunction "DIN_DIN") (pintype "bidirectional"))
    )
    (net (code "112") (name "Net-(LED109-PadDOUT)") (class "Default")
      (node (ref "LED109") (pin "DOUT") (pinfunction "DOUT_DOUT") (pintype "bidirectional"))
      (node (ref "LED110") (pin "DIN") (pinfunction "DIN_DIN") (pintype "bidirectional"))
    )
    (net (code "113") (name "Net-(LED110-PadDOUT)") (class "Default")
      (node (ref "LED110") (pin "DOUT") (pinfunction "DOUT_DOUT") (pintype "bidirectional"))
      (node (ref "LED111") (pin "DIN") (pinfunction "DIN_DIN") (pintype "bidirectional"))
    )
    (net (code "114") (name "Net-(LED111-PadDOUT)") (class "Default")
      (node (ref "LED111") (pin "DOUT") (pinfunction "DOUT_DOUT") (pintype "bidirectional"))
      (node (ref "LED112") (pin "DIN") (pinfunction "DIN_DIN") (pintype "bidirectional"))
    )
    (net (code "115") (name "Net-(LED112-PadDOUT)") (class "Default")
      (node (ref "LED112") (pin "DOUT") (pinfunction "DOUT_DOUT") (pintype "bidirectional"))
      (node (ref "LED113") (pin "DIN") (pinfunction "DIN_DIN") (pintype "bidirectional"))
    )
    (net (code "116") (name "Net-(LED113-PadDOUT)") (class "Default")
      (node (ref "LED113") (pin "DOUT") (pinfunction "DOUT_DOUT") (pintype "bidirectional"))
      (node (ref "LED114") (pin "DIN") (pinfunction "DIN_DIN") (pintype "bidirectional"))
    )
    (net (code "117") (name "Net-(LED114-PadDOUT)") (class "Default")
      (node (ref "LED114") (pin "DOUT") (pinfunction "DOUT_DOUT") (pintype "bidirectional"))
      (node (ref "LED115") (pin "DIN") (pinfunction "DIN_DIN") (pintype "bidirectional"))
    )
    (net (code "118") (name "Net-(LED115-PadDOUT)") (class "Default")
      (node (ref "LED115") (pin "DOUT") (pinfunction "DOUT_DOUT") (pintype "bidirectional"))
      (node (ref "LED116") (pin "DIN") (pinfunction "DIN_DIN") (pintype "bidirectional"))
    )
    (net (code "119") (name "Net-(LED116-PadDOUT)") (class "Default")
      (node (ref "LED116") (pin "DOUT") (pinfunction "DOUT_DOUT") (pintype "bidirectional"))
      (node (ref "LED117") (pin "DIN") (pinfunction "DIN_DIN") (pintype "bidirectional"))
    )
    (net (code "120") (name "Net-(LED117-PadDOUT)") (class "Default")
      (node (ref "LED117") (pin "DOUT") (pinfunction "DOUT_DOUT") (pintype "bidirectional"))
      (node (ref "LED118") (pin "DIN") (pinfunction "DIN_DIN") (pintype "bidirectional"))
    )
    (net (code "121") (name "Net-(LED118-PadDOUT)") (class "Default")
      (node (ref "LED118") (pin "DOUT") (pinfunction "DOUT_DOUT") (pintype "bidirectional"))
      (node (ref "LED119") (pin "DIN") (pinfunction "DIN_DIN") (pintype "bidirectional"))
    )
    (net (code "122") (name "Net-(LED119-PadDOUT)") (class "Default")
      (node (ref "LED119") (pin "DOUT") (pinfunction "DOUT_DOUT") (pintype "bidirectional"))
      (node (ref "LED120") (pin "DIN") (pinfunction "DIN_DIN") (pintype "bidirectional"))
    )
    (net (code "123") (name "Net-(LED120-PadDOUT)") (class "Default")
      (node (ref "LED120") (pin "DOUT") (pinfunction "DOUT_DOUT") (pintype "bidirectional"))
      (node (ref "LED121") (pin "DIN") (pinfunction "DIN_DIN") (pintype "bidirectional"))
    )
    (net (code "124") (name "Net-(LED121-PadDOUT)") (class "Default")
      (node (ref "LED121") (pin "DOUT") (pinfunction "DOUT_DOUT") (pintype "bidirectional"))
      (node (ref "LED122") (pin "DIN") (pinfunction "DIN_DIN") (pintype "bidirectional"))
    )
    (net (code "125") (name "Net-(LED122-PadDOUT)") (class "Default")
      (node (ref "LED122") (pin "DOUT") (pinfunction "DOUT_DOUT") (pintype "bidirectional"))
      (node (ref "LED123") (pin "DIN") (pinfunction "DIN_DIN") (pintype "bidirectional"))
    )
    (net (code "126") (name "Net-(LED123-PadDOUT)") (class "Default")
      (node (ref "LED123") (pin "DOUT") (pinfunction "DOUT_DOUT") (pintype "bidirectional"))
      (node (ref "LED124") (pin "DIN") (pinfunction "DIN_DIN") (pintype "bidirectional"))
    )
    (net (code "127") (name "Net-(LED124-PadDOUT)") (class "Default")
      (node (ref "LED124") (pin "DOUT") (pinfunction "DOUT_DOUT") (pintype "bidirectional"))
      (node (ref "LED125") (pin "DIN") (pinfunction "DIN_DIN") (pintype "bidirectional"))
    )
    (net (code "128") (name "Net-(LED125-PadDOUT)") (class "Default")
      (node (ref "LED125") (pin "DOUT") (pinfunction "DOUT_DOUT") (pintype "bidirectional"))
      (node (ref "LED126") (pin "DIN") (pinfunction "DIN_DIN") (pintype "bidirectional"))
    )
    (net (code "129") (name "Net-(LED126-PadDOUT)") (class "Default")
      (node (ref "LED126") (pin "DOUT") (pinfunction "DOUT_DOUT") (pintype "bidirectional"))
      (node (ref "LED127") (pin "DIN") (pinfunction "DIN_DIN") (pintype "bidirectional"))
    )
    (net (code "130") (name "Net-(LED127-PadDOUT)") (class "Default")
      (node (ref "LED127") (pin "DOUT") (pinfunction "DOUT_DOUT") (pintype "bidirectional"))
      (node (ref "LED128") (pin "DIN") (pinfunction "DIN_DIN") (pintype "bidirectional"))
    )
    (net (code "131") (name "unconnected-(JP1-Pad1)") (class "Default")
      (node (ref "JP1") (pin "1") (pinfunction "1_1") (pintype "passive"))
    )
    (net (code "132") (name "unconnected-(JP1-Pad3)") (class "Default")
      (node (ref "JP1") (pin "3") (pinfunction "3_3") (pintype "passive"))
    )
    (net (code "133") (name "unconnected-(JP2-Pad1)") (class "Default")
      (node (ref "JP2") (pin "1") (pinfunction "1_1") (pintype "passive"))
    )
    (net (code "134") (name "unconnected-(JP2-Pad2)") (class "Default")
      (node (ref "JP2") (pin "2") (pinfunction "2_2") (pintype "passive"))
    )
    (net (code "135") (name "unconnected-(JP2-Pad3)") (class "Default")
      (node (ref "JP2") (pin "3") (pinfunction "3_3") (pintype "passive"))
    )
    (net (code "136") (name "unconnected-(LED128-PadDOUT)") (class "Default")
      (node (ref "LED128") (pin "DOUT") (pinfunction "DOUT_DOUT") (pintype "bidirectional"))
    )
  )
)
